# zx80_SD_12_smd_build006_7_STM32.net
KiCad netlist of a schematic drawn in EAGLE
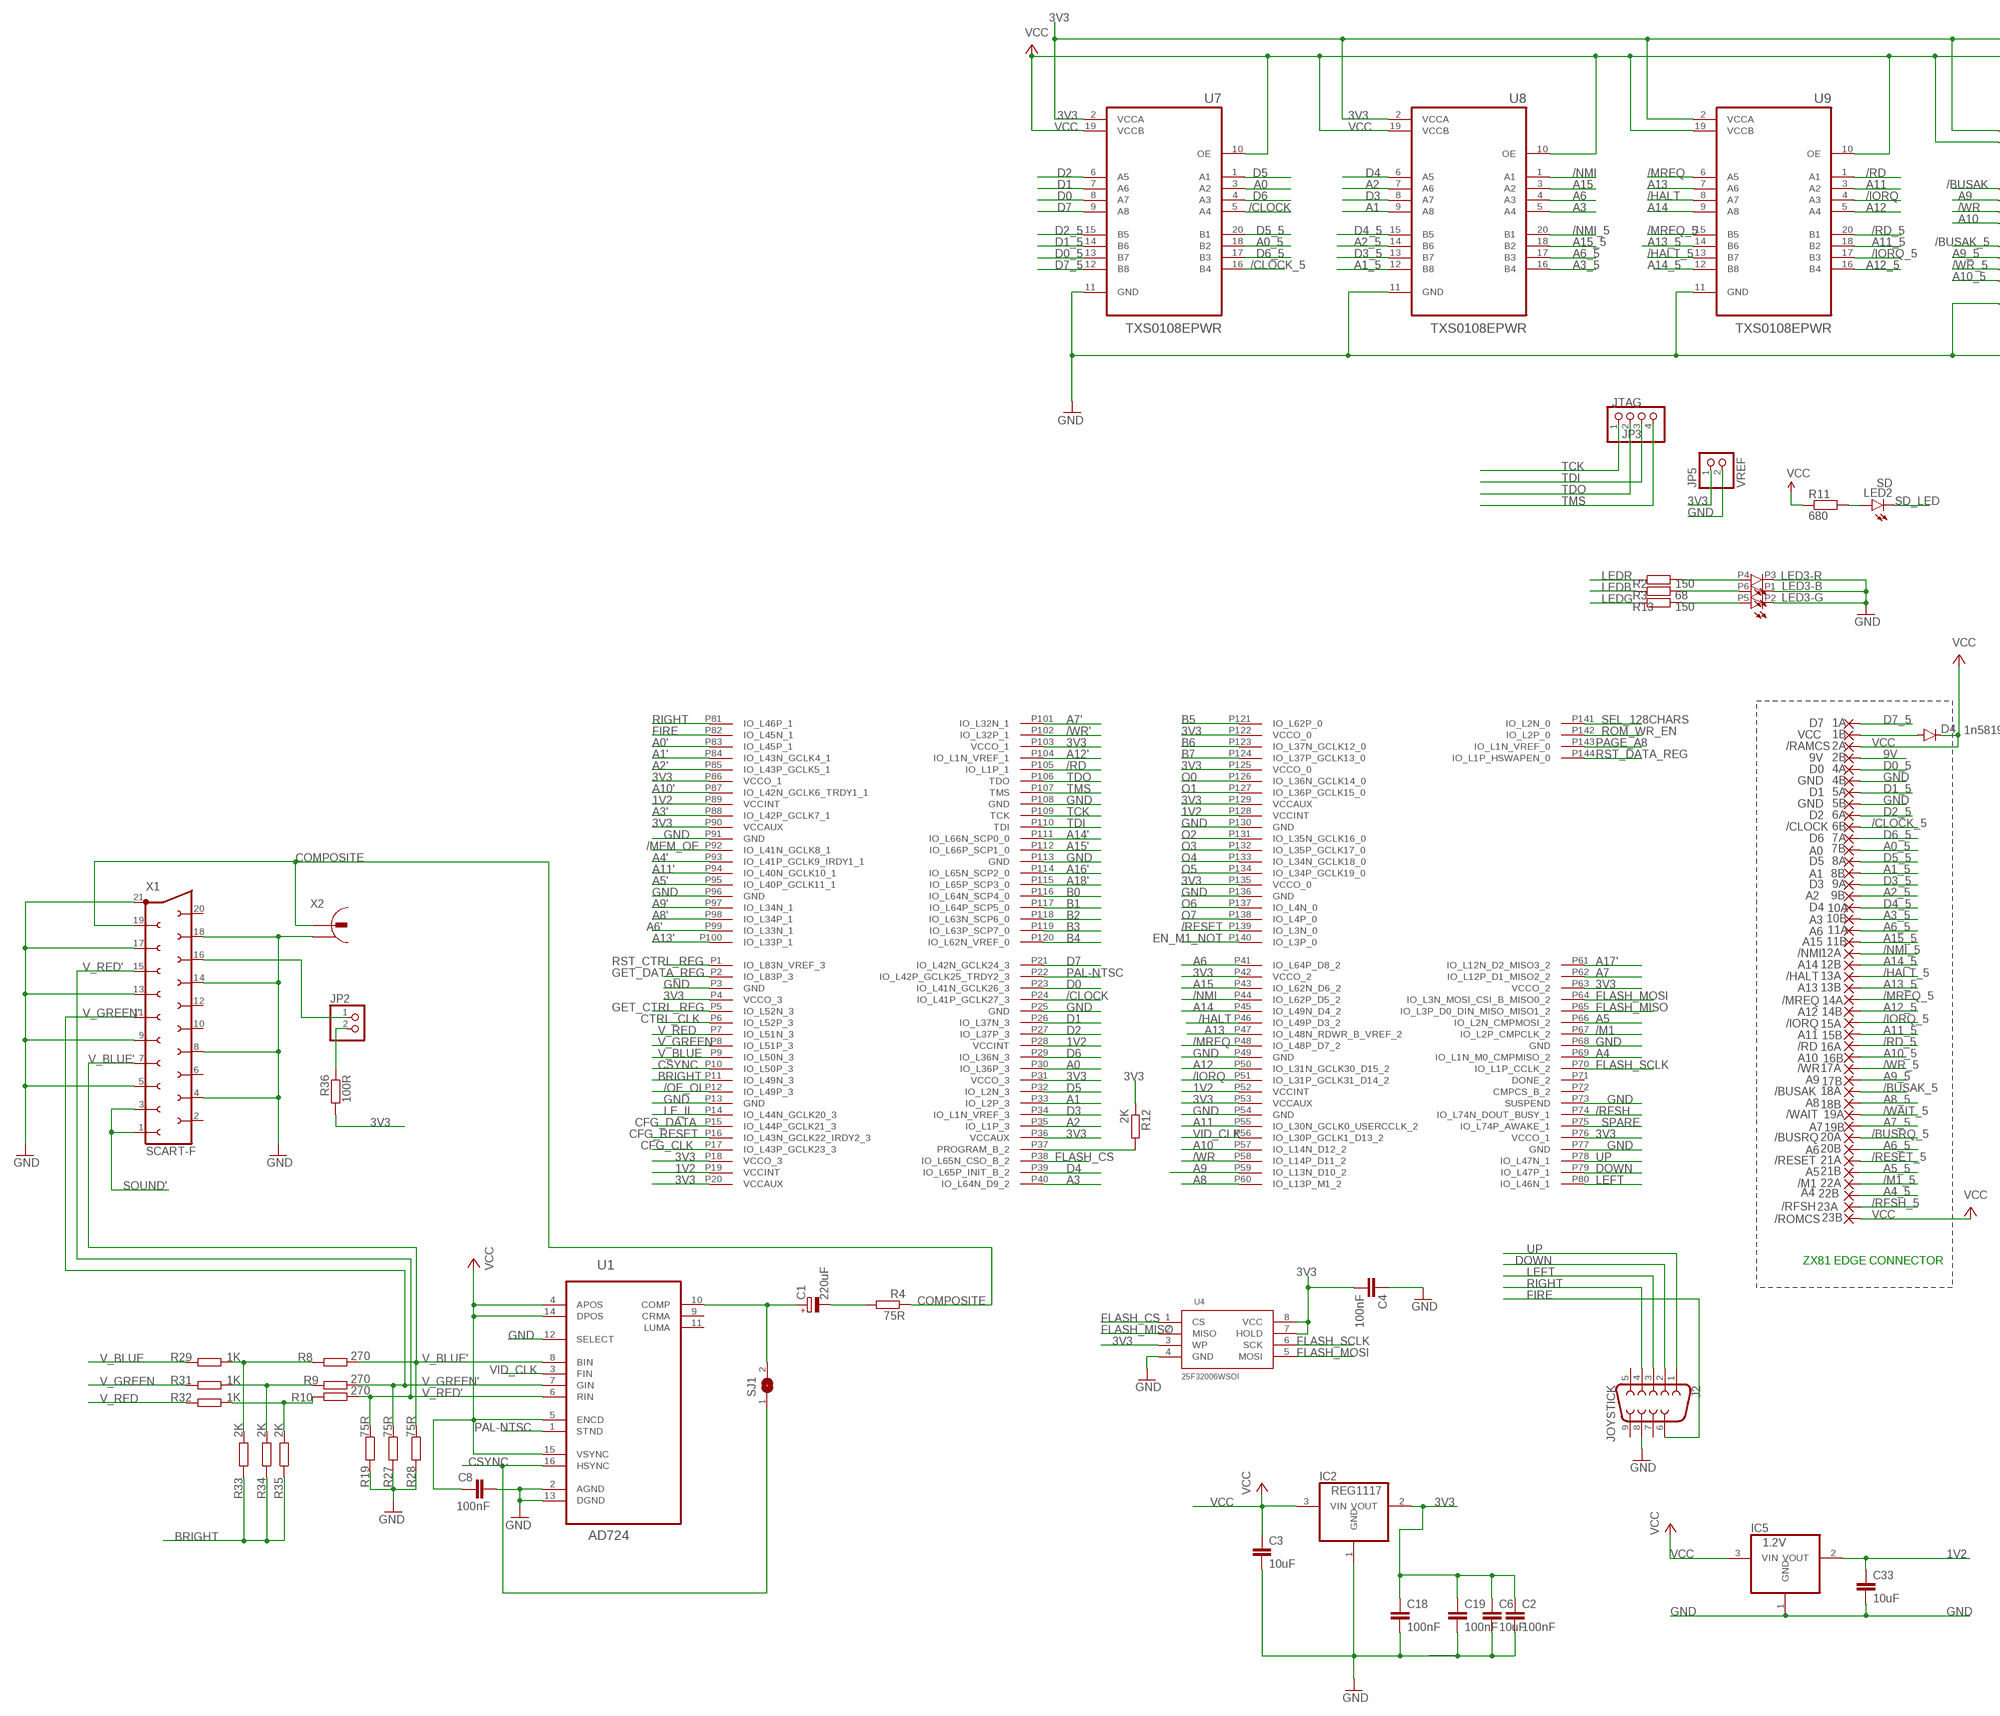
[diagram p0: schematic, sheet 1, part 1 of 2]
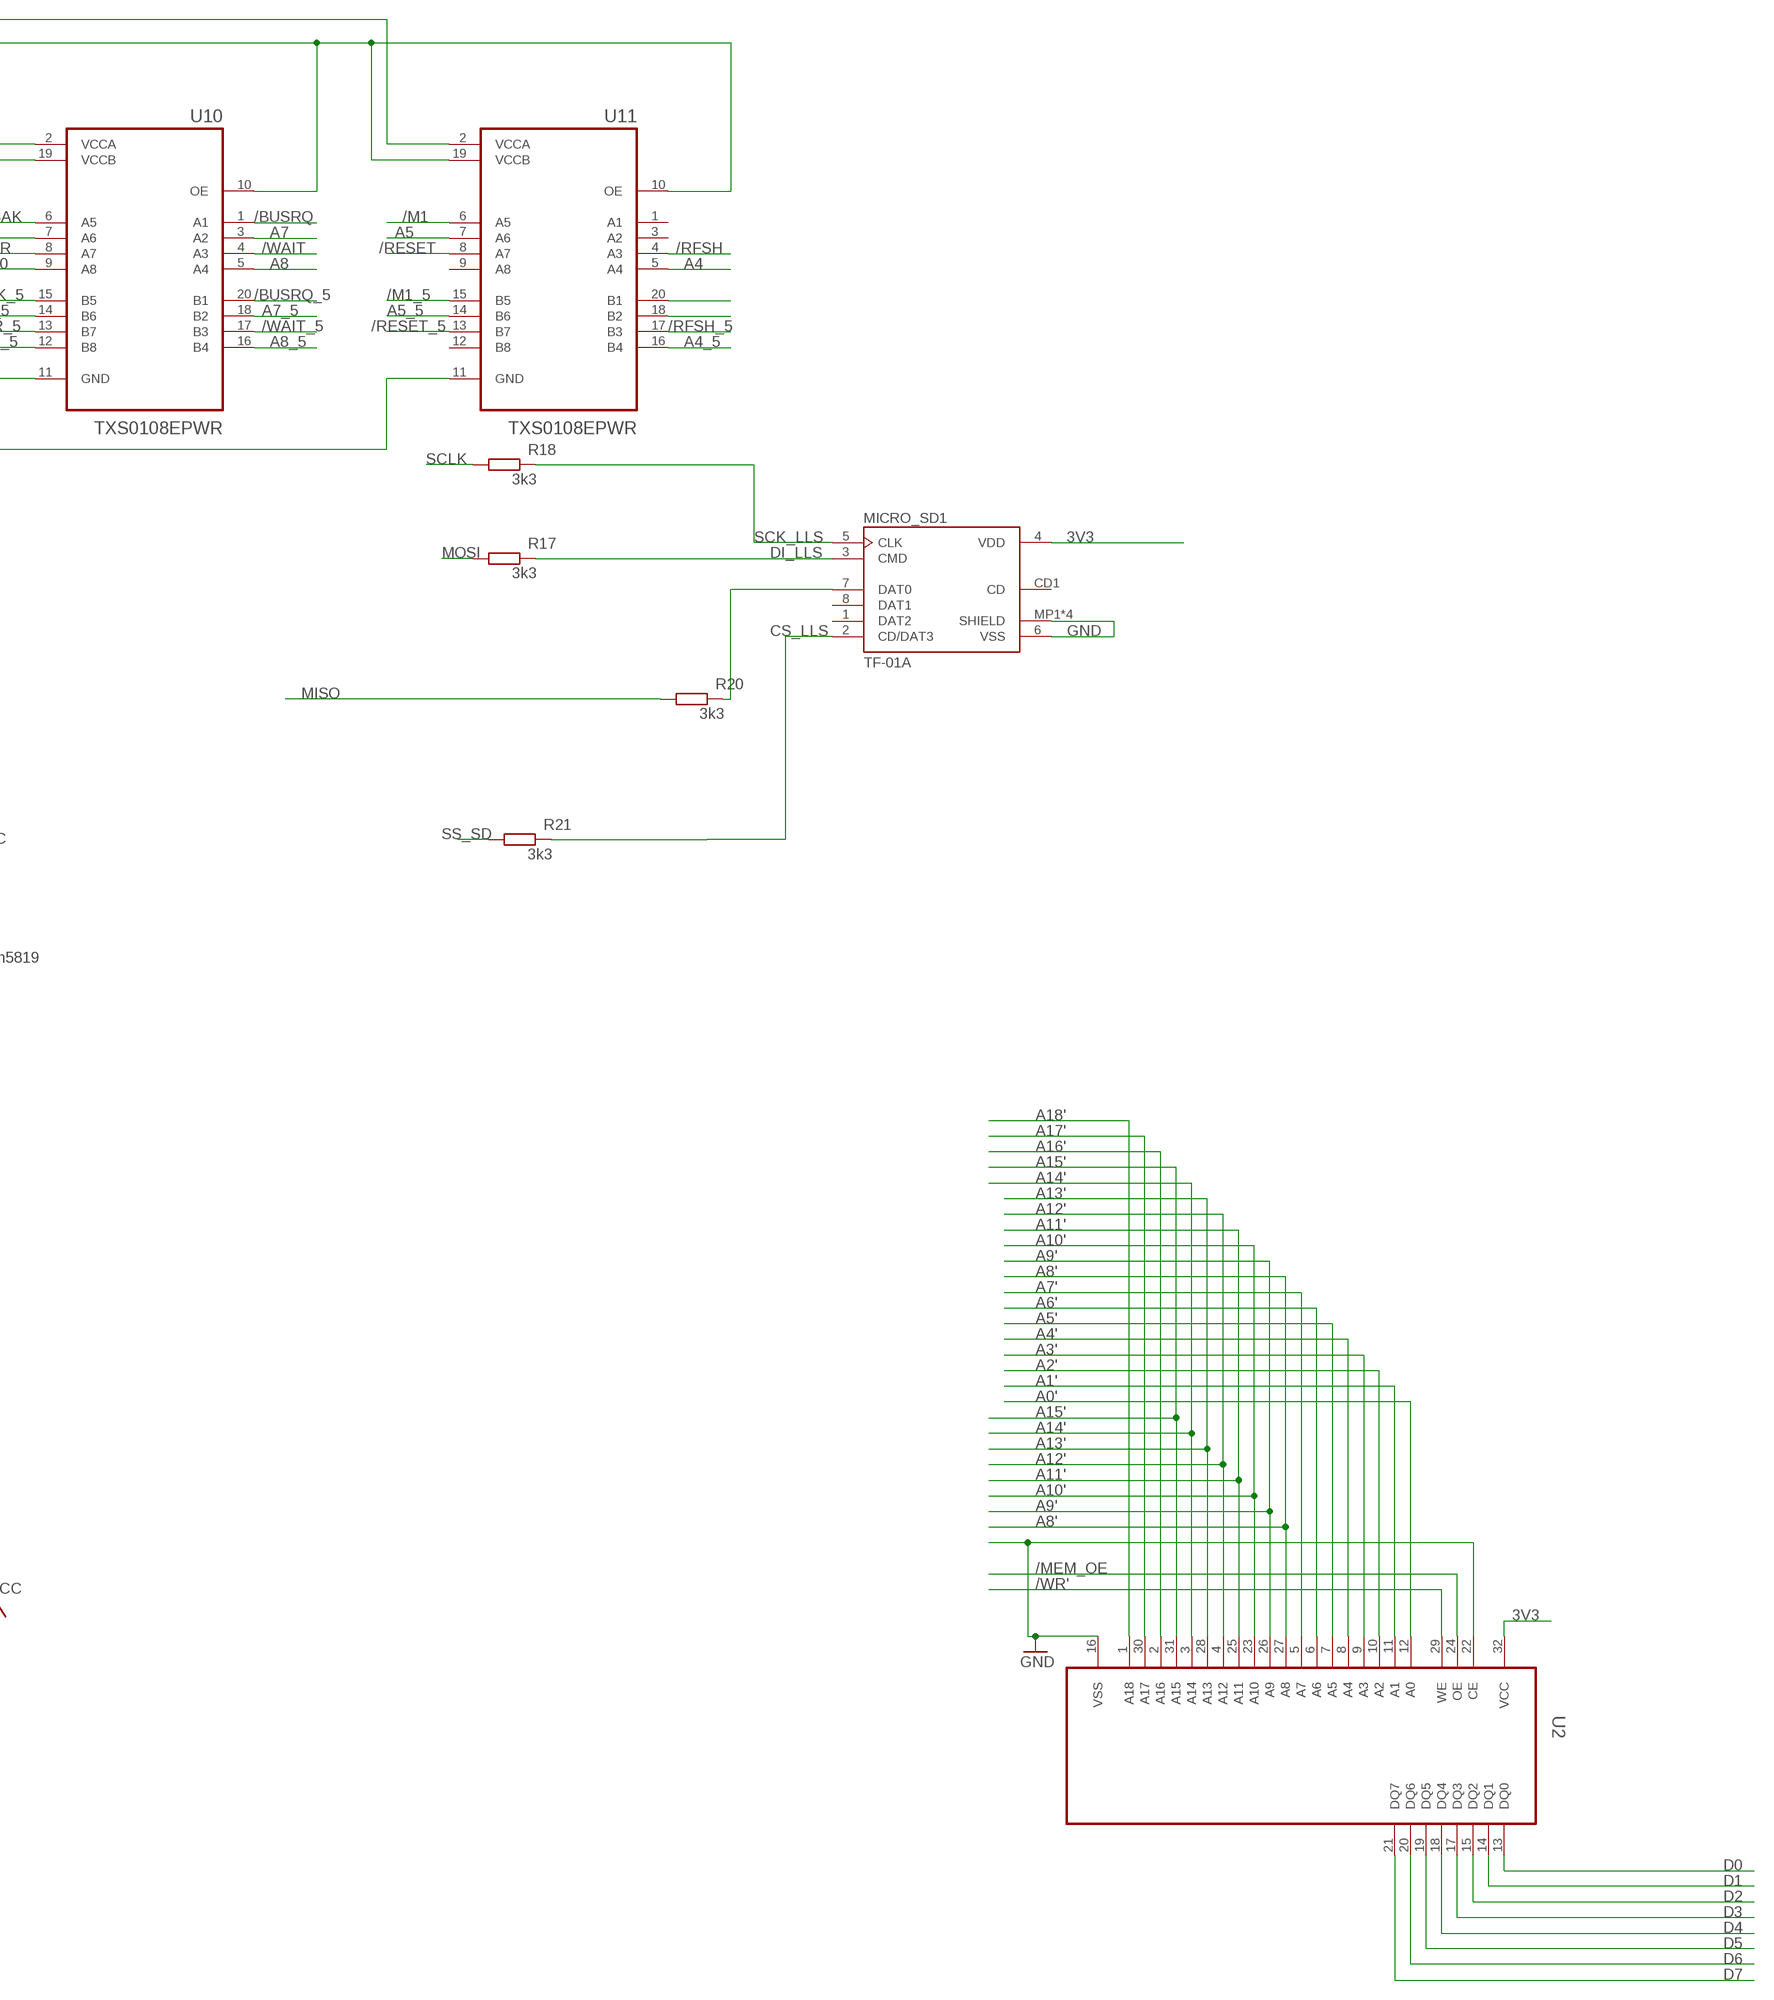
[diagram p1: schematic, sheet 1, part 2 of 2]
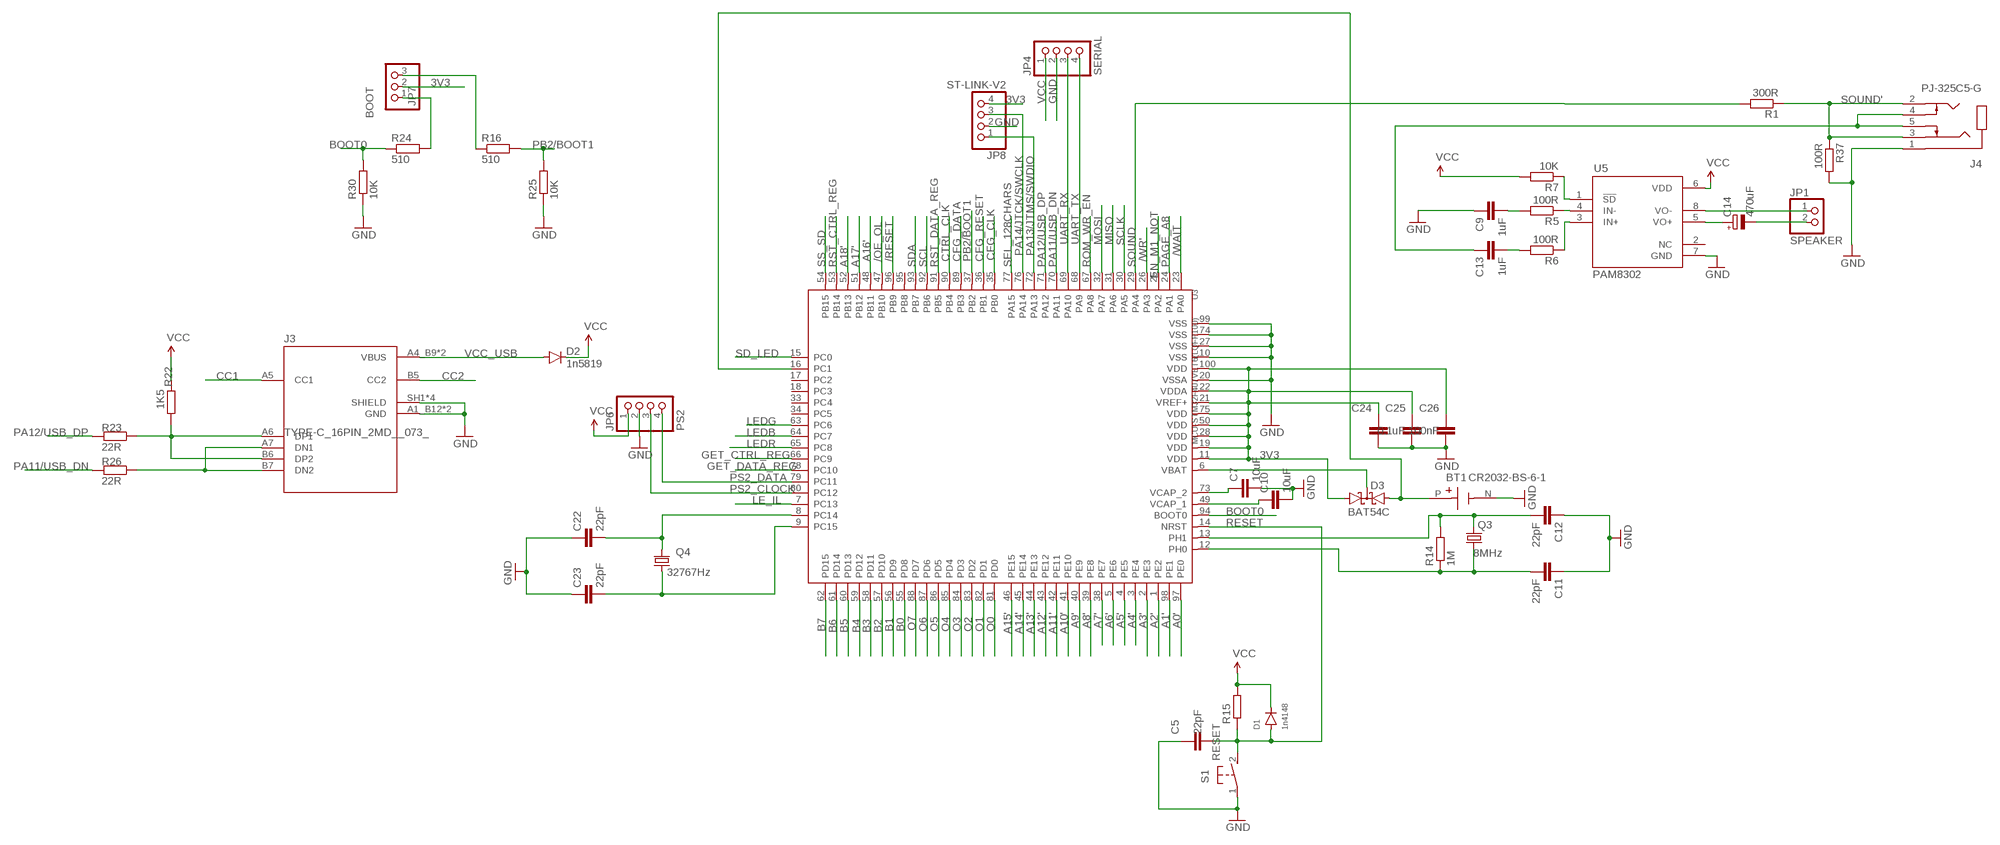
[diagram p2: schematic, sheet 2]

(export (version "E")
  (design (tool "Eeschema 10.0.6"))
  (components
    (comp (ref "BT1")
      (value "CR2032-BS-6-1")
      (footprint "eagle-import:BAT_CR2032-BS-6-1")
      (fields (field (name "MF") "Shenzhen Q&J Electronics Co. Ltd"))
      (libsource (lib "eagle-import") (part "CR2032-BS-6-1"))
    )
    (comp (ref "C5")
      (value "22pF")
      (footprint "eagle-import:C0603")
      (libsource (lib "eagle-import") (part "C-EUC0603"))
    )
    (comp (ref "C7")
      (value "10uF")
      (footprint "eagle-import:C0603")
      (libsource (lib "eagle-import") (part "C-EUC0603"))
    )
    (comp (ref "C9")
      (value "1uF")
      (footprint "eagle-import:C0603")
      (libsource (lib "eagle-import") (part "C-EUC0603"))
    )
    (comp (ref "C10")
      (value "10uF")
      (footprint "eagle-import:C0603")
      (libsource (lib "eagle-import") (part "C-EUC0603"))
    )
    (comp (ref "C11")
      (value "22pF")
      (footprint "eagle-import:C0603")
      (libsource (lib "eagle-import") (part "C-EUC0603"))
    )
    (comp (ref "C12")
      (value "22pF")
      (footprint "eagle-import:C0603")
      (libsource (lib "eagle-import") (part "C-EUC0603"))
    )
    (comp (ref "C13")
      (value "1uF")
      (footprint "eagle-import:C0603")
      (libsource (lib "eagle-import") (part "C-EUC0603"))
    )
    (comp (ref "C14")
      (value "470uF")
      (footprint "eagle-import:UD-6,3X7,7_NICHICON")
      (libsource (lib "eagle-import") (part "CPOL-EUUD-6,3X7,7"))
    )
    (comp (ref "C22")
      (value "22pF")
      (footprint "eagle-import:C0603")
      (libsource (lib "eagle-import") (part "C-EUC0603"))
    )
    (comp (ref "C23")
      (value "22pF")
      (footprint "eagle-import:C0603")
      (libsource (lib "eagle-import") (part "C-EUC0603"))
    )
    (comp (ref "C24")
      (value "0.1uF")
      (footprint "eagle-import:C0603")
      (libsource (lib "eagle-import") (part "C-EUC0603"))
    )
    (comp (ref "C25")
      (value "0.1uF")
      (footprint "eagle-import:C0603")
      (libsource (lib "eagle-import") (part "C-EUC0603"))
    )
    (comp (ref "C26")
      (value "100nF")
      (footprint "eagle-import:C0603")
      (libsource (lib "eagle-import") (part "C-EUC0603"))
    )
    (comp (ref "D1")
      (value "1n4148")
      (footprint "eagle-import:SOD123")
      (libsource (lib "eagle-import") (part "DIODE-SOD123"))
    )
    (comp (ref "D2")
      (value "1n5819")
      (footprint "eagle-import:SOD323-W")
      (libsource (lib "eagle-import") (part "DIODE-SOD323-W"))
    )
    (comp (ref "D3")
      (value "BAT54C")
      (footprint "eagle-import:SOT23")
      (libsource (lib "eagle-import") (part "BAT54C"))
    )
    (comp (ref "J3")
      (value "TYPE-C_16PIN_2MD__073_")
      (footprint "eagle-import:SHOUHAN_TYPE-C_16PIN_2MD__073_")
      (fields (field (name "MF") "Shouhan") (field (name "MP") "TYPE-C 16PIN 2MD (073)"))
      (libsource (lib "eagle-import") (part "TYPE-C_16PIN_2MD__073_"))
    )
    (comp (ref "J4")
      (value "PJ-325C5-G")
      (footprint "eagle-import:XKB_PJ-325C5-G")
      (fields (field (name "MF") "XKB Connection"))
      (libsource (lib "eagle-import") (part "PJ-325C5-G"))
    )
    (comp (ref "JP1")
      (value "SPEAKER")
      (footprint "eagle-import:1X02")
      (libsource (lib "eagle-import") (part "PINHD-1X2"))
    )
    (comp (ref "JP4")
      (value "SERIAL")
      (footprint "eagle-import:1X04")
      (libsource (lib "eagle-import") (part "PINHD-1X4"))
    )
    (comp (ref "JP6")
      (value "PS2")
      (footprint "eagle-import:1X04")
      (libsource (lib "eagle-import") (part "PINHD-1X4"))
    )
    (comp (ref "JP7")
      (value "BOOT")
      (footprint "eagle-import:1X03")
      (libsource (lib "eagle-import") (part "PINHD-1X3"))
    )
    (comp (ref "JP8")
      (value "ST-LINK-V2")
      (footprint "eagle-import:1X04")
      (libsource (lib "eagle-import") (part "PINHD-1X4"))
    )
    (comp (ref "Q3")
      (value "8MHz")
      (footprint "eagle-import:3.2X2.5_KX-7")
      (libsource (lib "eagle-import") (part "KX-7"))
    )
    (comp (ref "Q4")
      (value "32767Hz")
      (footprint "eagle-import:3.2X1.5")
      (libsource (lib "eagle-import") (part "KX-327-NHT"))
    )
    (comp (ref "R1")
      (value "300R")
      (footprint "eagle-import:R0603")
      (libsource (lib "eagle-import") (part "R-EU_R0603"))
    )
    (comp (ref "R5")
      (value "100R")
      (footprint "eagle-import:R0603")
      (libsource (lib "eagle-import") (part "R-EU_R0603"))
    )
    (comp (ref "R6")
      (value "100R")
      (footprint "eagle-import:R0603")
      (libsource (lib "eagle-import") (part "R-EU_R0603"))
    )
    (comp (ref "R7")
      (value "10K")
      (footprint "eagle-import:R0603")
      (libsource (lib "eagle-import") (part "R-EU_R0603"))
    )
    (comp (ref "R14")
      (value "1M")
      (footprint "eagle-import:R0402")
      (libsource (lib "eagle-import") (part "R-EU_R0402"))
    )
    (comp (ref "R15")
      (value "3k3")
      (footprint "eagle-import:R0603")
      (libsource (lib "eagle-import") (part "R-EU_R0603"))
    )
    (comp (ref "R16")
      (value "510")
      (footprint "eagle-import:R0603")
      (libsource (lib "eagle-import") (part "R-EU_R0603"))
    )
    (comp (ref "R22")
      (value "1K5")
      (footprint "eagle-import:R0603")
      (libsource (lib "eagle-import") (part "R-EU_R0603"))
    )
    (comp (ref "R23")
      (value "22R")
      (footprint "eagle-import:R0603")
      (libsource (lib "eagle-import") (part "R-EU_R0603"))
    )
    (comp (ref "R24")
      (value "510")
      (footprint "eagle-import:R0603")
      (libsource (lib "eagle-import") (part "R-EU_R0603"))
    )
    (comp (ref "R25")
      (value "10K")
      (footprint "eagle-import:R0603")
      (libsource (lib "eagle-import") (part "R-EU_R0603"))
    )
    (comp (ref "R26")
      (value "22R")
      (footprint "eagle-import:R0603")
      (libsource (lib "eagle-import") (part "R-EU_R0603"))
    )
    (comp (ref "R30")
      (value "10K")
      (footprint "eagle-import:R0603")
      (libsource (lib "eagle-import") (part "R-EU_R0603"))
    )
    (comp (ref "R37")
      (value "100R")
      (footprint "eagle-import:R0603")
      (libsource (lib "eagle-import") (part "R-EU_R0603"))
    )
    (comp (ref "S1")
      (value "RESET")
      (footprint "eagle-import:B3F-31XX")
      (fields (field (name "MPN") "B3F-3100"))
      (libsource (lib "eagle-import") (part "31-XX"))
    )
    (comp (ref "U3")
      (value "MCU-STM32F407VET6(LQFP100)")
      (footprint "eagle-import:LQFP100-0.5-13.8X13.8MM")
      (fields (field (name "MF") "STMicroelectronics") (field (name "MP") "STM32F407VET6"))
      (libsource (lib "eagle-import") (part "MCU-STM32F407VET6(LQFP100)"))
    )
    (comp (ref "U5")
      (value "PAM8302")
      (footprint "eagle-import:SOIC127P600X170-8N")
      (fields (field (name "MF") "Diodes Inc.") (field (name "MP") "PAM8302AADCR"))
      (libsource (lib "eagle-import") (part "PAM8302AADCR"))
    )
    (comp (ref "1A")
      (value "D7")
      (footprint "eagle-import:EDGEPIN")
      (libsource (lib "eagle-import") (part "SMD2EDGEPIN"))
    )
    (comp (ref "1B")
      (value "VCC")
      (footprint "eagle-import:EDGEPIN")
      (libsource (lib "eagle-import") (part "SMD2EDGEPIN"))
    )
    (comp (ref "2A")
      (value "/RAMCS")
      (footprint "eagle-import:EDGEPIN")
      (libsource (lib "eagle-import") (part "SMD2EDGEPIN"))
    )
    (comp (ref "2B")
      (value "9V")
      (footprint "eagle-import:EDGEPIN")
      (libsource (lib "eagle-import") (part "SMD2EDGEPIN"))
    )
    (comp (ref "4A")
      (value "D0")
      (footprint "eagle-import:EDGEPIN")
      (libsource (lib "eagle-import") (part "SMD2EDGEPIN"))
    )
    (comp (ref "4B")
      (value "GND")
      (footprint "eagle-import:EDGEPIN")
      (libsource (lib "eagle-import") (part "SMD2EDGEPIN"))
    )
    (comp (ref "5A")
      (value "D1")
      (footprint "eagle-import:EDGEPIN")
      (libsource (lib "eagle-import") (part "SMD2EDGEPIN"))
    )
    (comp (ref "5B")
      (value "GND")
      (footprint "eagle-import:EDGEPIN")
      (libsource (lib "eagle-import") (part "SMD2EDGEPIN"))
    )
    (comp (ref "6A")
      (value "D2")
      (footprint "eagle-import:EDGEPIN")
      (libsource (lib "eagle-import") (part "SMD2EDGEPIN"))
    )
    (comp (ref "6B")
      (value "/CLOCK")
      (footprint "eagle-import:EDGEPIN")
      (libsource (lib "eagle-import") (part "SMD2EDGEPIN"))
    )
    (comp (ref "7A")
      (value "D6")
      (footprint "eagle-import:EDGEPIN")
      (libsource (lib "eagle-import") (part "SMD2EDGEPIN"))
    )
    (comp (ref "7B")
      (value "A0")
      (footprint "eagle-import:EDGEPIN")
      (libsource (lib "eagle-import") (part "SMD2EDGEPIN"))
    )
    (comp (ref "8A")
      (value "D5")
      (footprint "eagle-import:EDGEPIN")
      (libsource (lib "eagle-import") (part "SMD2EDGEPIN"))
    )
    (comp (ref "8B")
      (value "A1")
      (footprint "eagle-import:EDGEPIN")
      (libsource (lib "eagle-import") (part "SMD2EDGEPIN"))
    )
    (comp (ref "9A")
      (value "D3")
      (footprint "eagle-import:EDGEPIN")
      (libsource (lib "eagle-import") (part "SMD2EDGEPIN"))
    )
    (comp (ref "9B")
      (value "A2")
      (footprint "eagle-import:EDGEPIN")
      (libsource (lib "eagle-import") (part "SMD2EDGEPIN"))
    )
    (comp (ref "10A")
      (value "D4")
      (footprint "eagle-import:EDGEPIN")
      (libsource (lib "eagle-import") (part "SMD2EDGEPIN"))
    )
    (comp (ref "10B")
      (value "A3")
      (footprint "eagle-import:EDGEPIN")
      (libsource (lib "eagle-import") (part "SMD2EDGEPIN"))
    )
    (comp (ref "11A")
      (value "A6")
      (footprint "eagle-import:EDGEPIN")
      (libsource (lib "eagle-import") (part "SMD2EDGEPIN"))
    )
    (comp (ref "11B")
      (value "A15")
      (footprint "eagle-import:EDGEPIN")
      (libsource (lib "eagle-import") (part "SMD2EDGEPIN"))
    )
    (comp (ref "12A")
      (value "/NMI")
      (footprint "eagle-import:EDGEPIN")
      (libsource (lib "eagle-import") (part "SMD2EDGEPIN"))
    )
    (comp (ref "12B")
      (value "A14")
      (footprint "eagle-import:EDGEPIN")
      (libsource (lib "eagle-import") (part "SMD2EDGEPIN"))
    )
    (comp (ref "13A")
      (value "/HALT")
      (footprint "eagle-import:EDGEPIN")
      (libsource (lib "eagle-import") (part "SMD2EDGEPIN"))
    )
    (comp (ref "13B")
      (value "A13")
      (footprint "eagle-import:EDGEPIN")
      (libsource (lib "eagle-import") (part "SMD2EDGEPIN"))
    )
    (comp (ref "14A")
      (value "/MREQ")
      (footprint "eagle-import:EDGEPIN")
      (libsource (lib "eagle-import") (part "SMD2EDGEPIN"))
    )
    (comp (ref "14B")
      (value "A12")
      (footprint "eagle-import:EDGEPIN")
      (libsource (lib "eagle-import") (part "SMD2EDGEPIN"))
    )
    (comp (ref "15A")
      (value "/IORQ")
      (footprint "eagle-import:EDGEPIN")
      (libsource (lib "eagle-import") (part "SMD2EDGEPIN"))
    )
    (comp (ref "15B")
      (value "A11")
      (footprint "eagle-import:EDGEPIN")
      (libsource (lib "eagle-import") (part "SMD2EDGEPIN"))
    )
    (comp (ref "16A")
      (value "/RD")
      (footprint "eagle-import:EDGEPIN")
      (libsource (lib "eagle-import") (part "SMD2EDGEPIN"))
    )
    (comp (ref "16B")
      (value "A10")
      (footprint "eagle-import:EDGEPIN")
      (libsource (lib "eagle-import") (part "SMD2EDGEPIN"))
    )
    (comp (ref "17A")
      (value "/WR")
      (footprint "eagle-import:EDGEPIN")
      (libsource (lib "eagle-import") (part "SMD2EDGEPIN"))
    )
    (comp (ref "17B")
      (value "A9")
      (footprint "eagle-import:EDGEPIN")
      (libsource (lib "eagle-import") (part "SMD2EDGEPIN"))
    )
    (comp (ref "18A")
      (value "/BUSAK")
      (footprint "eagle-import:EDGEPIN")
      (libsource (lib "eagle-import") (part "SMD2EDGEPIN"))
    )
    (comp (ref "18B")
      (value "A8")
      (footprint "eagle-import:EDGEPIN")
      (libsource (lib "eagle-import") (part "SMD2EDGEPIN"))
    )
    (comp (ref "19A")
      (value "/WAIT")
      (footprint "eagle-import:EDGEPIN")
      (libsource (lib "eagle-import") (part "SMD2EDGEPIN"))
    )
    (comp (ref "19B")
      (value "A7")
      (footprint "eagle-import:EDGEPIN")
      (libsource (lib "eagle-import") (part "SMD2EDGEPIN"))
    )
    (comp (ref "20A")
      (value "/BUSRQ")
      (footprint "eagle-import:EDGEPIN")
      (libsource (lib "eagle-import") (part "SMD2EDGEPIN"))
    )
    (comp (ref "20B")
      (value "A6")
      (footprint "eagle-import:EDGEPIN")
      (libsource (lib "eagle-import") (part "SMD2EDGEPIN"))
    )
    (comp (ref "21A")
      (value "/RESET")
      (footprint "eagle-import:EDGEPIN")
      (libsource (lib "eagle-import") (part "SMD2EDGEPIN"))
    )
    (comp (ref "21B")
      (value "A5")
      (footprint "eagle-import:EDGEPIN")
      (libsource (lib "eagle-import") (part "SMD2EDGEPIN"))
    )
    (comp (ref "22A")
      (value "/M1")
      (footprint "eagle-import:EDGEPIN")
      (libsource (lib "eagle-import") (part "SMD2EDGEPIN"))
    )
    (comp (ref "22B")
      (value "A4")
      (footprint "eagle-import:EDGEPIN")
      (libsource (lib "eagle-import") (part "SMD2EDGEPIN"))
    )
    (comp (ref "23A")
      (value "/RFSH")
      (footprint "eagle-import:EDGEPIN")
      (libsource (lib "eagle-import") (part "SMD2EDGEPIN"))
    )
    (comp (ref "23B")
      (value "/ROMCS")
      (footprint "eagle-import:EDGEPIN")
      (libsource (lib "eagle-import") (part "SMD2EDGEPIN"))
    )
    (comp (ref "C1")
      (value "220uF")
      (footprint "eagle-import:UD-6,3X7,7_NICHICON")
      (libsource (lib "eagle-import") (part "CPOL-EUUD-6,3X7,7"))
    )
    (comp (ref "C2")
      (value "100nF")
      (footprint "eagle-import:C0603")
      (libsource (lib "eagle-import") (part "C-EUC0603"))
    )
    (comp (ref "C3")
      (value "10uF")
      (footprint "eagle-import:C0603")
      (libsource (lib "eagle-import") (part "C-EUC0603"))
    )
    (comp (ref "C4")
      (value "100nF")
      (footprint "eagle-import:C0603")
      (libsource (lib "eagle-import") (part "C-EUC0603"))
    )
    (comp (ref "C6")
      (value "10uF")
      (footprint "eagle-import:C0603")
      (libsource (lib "eagle-import") (part "C-EUC0603"))
    )
    (comp (ref "C8")
      (value "100nF")
      (footprint "eagle-import:C0603K")
      (libsource (lib "eagle-import") (part "C-EUC0603K"))
    )
    (comp (ref "C18")
      (value "100nF")
      (footprint "eagle-import:C0603")
      (libsource (lib "eagle-import") (part "C-EUC0603"))
    )
    (comp (ref "C19")
      (value "100nF")
      (footprint "eagle-import:C0603")
      (libsource (lib "eagle-import") (part "C-EUC0603"))
    )
    (comp (ref "C33")
      (value "10uF")
      (footprint "eagle-import:C0603")
      (libsource (lib "eagle-import") (part "C-EUC0603"))
    )
    (comp (ref "D4")
      (value "1n5819")
      (footprint "eagle-import:SOD323-W")
      (libsource (lib "eagle-import") (part "DIODE-SOD323-W"))
    )
    (comp (ref "IC2")
      (value "REG1117")
      (footprint "eagle-import:SOT223")
      (libsource (lib "eagle-import") (part "REG1117"))
    )
    (comp (ref "IC5")
      (value "1.2V")
      (footprint "eagle-import:SOT223")
      (fields (field (name "MPN") "REG1117"))
      (libsource (lib "eagle-import") (part "REG1117"))
    )
    (comp (ref "J2")
      (value "JOYSTICK")
      (footprint "eagle-import:DB9_MALE")
      (libsource (lib "eagle-import") (part "DB9MALE"))
    )
    (comp (ref "JP2")
      (value "PINHD-1X2")
      (footprint "eagle-import:1X02")
      (libsource (lib "eagle-import") (part "PINHD-1X2"))
    )
    (comp (ref "JP3")
      (value "JTAG")
      (footprint "eagle-import:1X04")
      (libsource (lib "eagle-import") (part "PINHD-1X4"))
    )
    (comp (ref "JP5")
      (value "VREF")
      (footprint "eagle-import:1X02")
      (libsource (lib "eagle-import") (part "PINHD-1X2"))
    )
    (comp (ref "LED2")
      (value "SD")
      (footprint "eagle-import:CHIPLED_0805")
      (libsource (lib "eagle-import") (part "LEDCHIPLED_0805"))
    )
    (comp (ref "LED3")
      (value "STATUS")
      (footprint "eagle-import:3535-PLCC6")
      (libsource (lib "eagle-import") (part "3535RGB3535RGB"))
    )
    (comp (ref "MICRO_SD1")
      (value "TF-01A")
      (footprint "eagle-import:TF-01A")
      (fields (field (name "MF") "HRO Electronics Co., Ltd."))
      (libsource (lib "eagle-import") (part "TF-01A"))
    )
    (comp (ref "R2")
      (value "150")
      (footprint "eagle-import:R0603")
      (libsource (lib "eagle-import") (part "R-EU_R0603"))
    )
    (comp (ref "R3")
      (value "68")
      (footprint "eagle-import:R0603")
      (libsource (lib "eagle-import") (part "R-EU_R0603"))
    )
    (comp (ref "R4")
      (value "75R")
      (footprint "eagle-import:R0603")
      (libsource (lib "eagle-import") (part "R-EU_R0603"))
    )
    (comp (ref "R8")
      (value "270")
      (footprint "eagle-import:R0603")
      (libsource (lib "eagle-import") (part "R-EU_R0603"))
    )
    (comp (ref "R9")
      (value "270")
      (footprint "eagle-import:R0603")
      (libsource (lib "eagle-import") (part "R-EU_R0603"))
    )
    (comp (ref "R10")
      (value "270")
      (footprint "eagle-import:R0603")
      (libsource (lib "eagle-import") (part "R-EU_R0603"))
    )
    (comp (ref "R11")
      (value "680")
      (footprint "eagle-import:R0603")
      (libsource (lib "eagle-import") (part "R-EU_R0603"))
    )
    (comp (ref "R12")
      (value "2K")
      (footprint "eagle-import:R0402")
      (libsource (lib "eagle-import") (part "R-EU_R0402"))
    )
    (comp (ref "R13")
      (value "150")
      (footprint "eagle-import:R0603")
      (libsource (lib "eagle-import") (part "R-EU_R0603"))
    )
    (comp (ref "R17")
      (value "3k3")
      (footprint "eagle-import:R0603")
      (libsource (lib "eagle-import") (part "R-EU_R0603"))
    )
    (comp (ref "R18")
      (value "3k3")
      (footprint "eagle-import:R0603")
      (libsource (lib "eagle-import") (part "R-EU_R0603"))
    )
    (comp (ref "R19")
      (value "75R")
      (footprint "eagle-import:R0603")
      (libsource (lib "eagle-import") (part "R-EU_R0603"))
    )
    (comp (ref "R20")
      (value "3k3")
      (footprint "eagle-import:R0603")
      (libsource (lib "eagle-import") (part "R-EU_R0603"))
    )
    (comp (ref "R21")
      (value "3k3")
      (footprint "eagle-import:R0603")
      (libsource (lib "eagle-import") (part "R-EU_R0603"))
    )
    (comp (ref "R27")
      (value "75R")
      (footprint "eagle-import:R0603")
      (libsource (lib "eagle-import") (part "R-EU_R0603"))
    )
    (comp (ref "R28")
      (value "75R")
      (footprint "eagle-import:R0603")
      (libsource (lib "eagle-import") (part "R-EU_R0603"))
    )
    (comp (ref "R29")
      (value "1K")
      (footprint "eagle-import:R0402")
      (libsource (lib "eagle-import") (part "R-EU_R0402"))
    )
    (comp (ref "R31")
      (value "1K")
      (footprint "eagle-import:R0402")
      (libsource (lib "eagle-import") (part "R-EU_R0402"))
    )
    (comp (ref "R32")
      (value "1K")
      (footprint "eagle-import:R0402")
      (libsource (lib "eagle-import") (part "R-EU_R0402"))
    )
    (comp (ref "R33")
      (value "2K")
      (footprint "eagle-import:R0402")
      (libsource (lib "eagle-import") (part "R-EU_R0402"))
    )
    (comp (ref "R34")
      (value "2K")
      (footprint "eagle-import:R0402")
      (libsource (lib "eagle-import") (part "R-EU_R0402"))
    )
    (comp (ref "R35")
      (value "2K")
      (footprint "eagle-import:R0402")
      (libsource (lib "eagle-import") (part "R-EU_R0402"))
    )
    (comp (ref "R36")
      (value "100R")
      (footprint "eagle-import:R0603")
      (libsource (lib "eagle-import") (part "R-EU_R0603"))
    )
    (comp (ref "SJ1") (value "SJ") (footprint "eagle-import:SJ") (libsource (lib "eagle-import") (part "SJ")))
    (comp (ref "U1")
      (value "AD724")
      (footprint "eagle-import:SOIC127P1032X265-16N")
      (fields (field (name "MF") "Analog Devices") (field (name "MP") "AD724JR"))
      (libsource (lib "eagle-import") (part "AD724JRZ"))
    )
    (comp (ref "U2")
      (value "AS6C4008")
      (footprint "eagle-import:SOP32-5")
      (libsource (lib "eagle-import") (part "AS6C4008-55SINSOP5"))
    )
    (comp (ref "U4")
      (value "25F32006WSOI")
      (footprint "eagle-import:SO08-EIAJ")
      (libsource (lib "eagle-import") (part "SPI_FLASH-X25XXSMD1"))
    )
    (comp (ref "U6")
      (value "XC6SLX9-2TQG144C")
      (footprint "eagle-import:TQ144")
      (fields (field (name "MF") "Xilinx Inc."))
      (libsource (lib "eagle-import") (part "XC6SLX9-2TQG144C"))
    )
    (comp (ref "U7")
      (value "TXS0108EPWR")
      (footprint "eagle-import:SOP65P640X120-20N")
      (fields (field (name "MF") "Texas Instruments"))
      (libsource (lib "eagle-import") (part "TXS0108EPWR"))
    )
    (comp (ref "U8")
      (value "TXS0108EPWR")
      (footprint "eagle-import:SOP65P640X120-20N")
      (fields (field (name "MF") "Texas Instruments"))
      (libsource (lib "eagle-import") (part "TXS0108EPWR"))
    )
    (comp (ref "U9")
      (value "TXS0108EPWR")
      (footprint "eagle-import:SOP65P640X120-20N")
      (fields (field (name "MF") "Texas Instruments"))
      (libsource (lib "eagle-import") (part "TXS0108EPWR"))
    )
    (comp (ref "U10")
      (value "TXS0108EPWR")
      (footprint "eagle-import:SOP65P640X120-20N")
      (fields (field (name "MF") "Texas Instruments"))
      (libsource (lib "eagle-import") (part "TXS0108EPWR"))
    )
    (comp (ref "U11")
      (value "TXS0108EPWR")
      (footprint "eagle-import:SOP65P640X120-20N")
      (fields (field (name "MF") "Texas Instruments"))
      (libsource (lib "eagle-import") (part "TXS0108EPWR"))
    )
    (comp (ref "X1")
      (value "SCART-F")
      (footprint "eagle-import:SCART-F")
      (libsource (lib "eagle-import") (part "SCART-F"))
    )
    (comp (ref "X2")
      (value "CON-CONRAD_736880-2P")
      (footprint "eagle-import:3P")
      (libsource (lib "eagle-import") (part "CON-CONRAD_736880-2P"))
    )
  )
  (nets
    (net (code "1") (name "1V2") (class "Default")
      (node (ref "C33") (pin "1") (pinfunction "1_1") (pintype "passive"))
      (node (ref "IC5") (pin "2") (pinfunction "VOUT_2") (pintype "output"))
      (node (ref "U6") (pin "P128") (pinfunction "VCCINT_P128") (pintype "bidirectional"))
      (node (ref "U6") (pin "P19") (pinfunction "VCCINT_P19") (pintype "bidirectional"))
      (node (ref "U6") (pin "P28") (pinfunction "VCCINT_P28") (pintype "bidirectional"))
      (node (ref "U6") (pin "P52") (pinfunction "VCCINT_P52") (pintype "bidirectional"))
      (node (ref "U6") (pin "P89") (pinfunction "VCCINT_P89") (pintype "bidirectional"))
    )
    (net (code "2") (name "3V3") (class "Default")
      (node (ref "C18") (pin "1") (pinfunction "1_1") (pintype "passive"))
      (node (ref "C19") (pin "1") (pinfunction "1_1") (pintype "passive"))
      (node (ref "C2") (pin "1") (pinfunction "1_1") (pintype "passive"))
      (node (ref "C24") (pin "1") (pinfunction "1_1") (pintype "passive"))
      (node (ref "C25") (pin "1") (pinfunction "1_1") (pintype "passive"))
      (node (ref "C26") (pin "1") (pinfunction "1_1") (pintype "passive"))
      (node (ref "C4") (pin "2") (pinfunction "2_2") (pintype "passive"))
      (node (ref "C6") (pin "1") (pinfunction "1_1") (pintype "passive"))
      (node (ref "D3") (pin "1") (pinfunction "A1_1") (pintype "passive"))
      (node (ref "IC2") (pin "2") (pinfunction "VOUT_2") (pintype "output"))
      (node (ref "JP5") (pin "1") (pinfunction "1_1") (pintype "passive"))
      (node (ref "JP7") (pin "2") (pinfunction "2_2") (pintype "passive"))
      (node (ref "JP8") (pin "4") (pinfunction "4_4") (pintype "passive"))
      (node (ref "MICRO_SD1") (pin "4") (pinfunction "VDD_4") (pintype "power_in"))
      (node (ref "R12") (pin "1") (pinfunction "1_1") (pintype "passive"))
      (node (ref "R36") (pin "2") (pinfunction "2_2") (pintype "passive"))
      (node (ref "U10") (pin "2") (pinfunction "VCCA_2") (pintype "power_in"))
      (node (ref "U11") (pin "2") (pinfunction "VCCA_2") (pintype "power_in"))
      (node (ref "U2") (pin "32") (pinfunction "VCC_32") (pintype "power_in"))
      (node (ref "U3") (pin "100") (pinfunction "VDD_100") (pintype "bidirectional"))
      (node (ref "U3") (pin "11") (pinfunction "VDD_11") (pintype "bidirectional"))
      (node (ref "U3") (pin "19") (pinfunction "VDD_19") (pintype "bidirectional"))
      (node (ref "U3") (pin "21") (pinfunction "VREF+_21") (pintype "bidirectional"))
      (node (ref "U3") (pin "22") (pinfunction "VDDA_22") (pintype "bidirectional"))
      (node (ref "U3") (pin "28") (pinfunction "VDD_28") (pintype "bidirectional"))
      (node (ref "U3") (pin "50") (pinfunction "VDD_50") (pintype "bidirectional"))
      (node (ref "U3") (pin "75") (pinfunction "VDD_75") (pintype "bidirectional"))
      (node (ref "U4") (pin "3") (pinfunction "WP_3") (pintype "bidirectional"))
      (node (ref "U4") (pin "7") (pinfunction "HOLD_7") (pintype "bidirectional"))
      (node (ref "U4") (pin "8") (pinfunction "VCC_8") (pintype "power_in"))
      (node (ref "U6") (pin "P103") (pinfunction "VCCO_1_P103") (pintype "bidirectional"))
      (node (ref "U6") (pin "P122") (pinfunction "VCCO_0_P122") (pintype "bidirectional"))
      (node (ref "U6") (pin "P125") (pinfunction "VCCO_0_P125") (pintype "bidirectional"))
      (node (ref "U6") (pin "P129") (pinfunction "VCCAUX_P129") (pintype "bidirectional"))
      (node (ref "U6") (pin "P135") (pinfunction "VCCO_0_P135") (pintype "bidirectional"))
      (node (ref "U6") (pin "P18") (pinfunction "VCCO_3_P18") (pintype "bidirectional"))
      (node (ref "U6") (pin "P20") (pinfunction "VCCAUX_P20") (pintype "bidirectional"))
      (node (ref "U6") (pin "P31") (pinfunction "VCCO_3_P31") (pintype "bidirectional"))
      (node (ref "U6") (pin "P36") (pinfunction "VCCAUX_P36") (pintype "bidirectional"))
      (node (ref "U6") (pin "P4") (pinfunction "VCCO_3_P4") (pintype "bidirectional"))
      (node (ref "U6") (pin "P42") (pinfunction "VCCO_2_P42") (pintype "bidirectional"))
      (node (ref "U6") (pin "P53") (pinfunction "VCCAUX_P53") (pintype "bidirectional"))
      (node (ref "U6") (pin "P63") (pinfunction "VCCO_2_P63") (pintype "bidirectional"))
      (node (ref "U6") (pin "P76") (pinfunction "VCCO_1_P76") (pintype "bidirectional"))
      (node (ref "U6") (pin "P86") (pinfunction "VCCO_1_P86") (pintype "bidirectional"))
      (node (ref "U6") (pin "P90") (pinfunction "VCCAUX_P90") (pintype "bidirectional"))
      (node (ref "U7") (pin "2") (pinfunction "VCCA_2") (pintype "power_in"))
      (node (ref "U8") (pin "2") (pinfunction "VCCA_2") (pintype "power_in"))
      (node (ref "U9") (pin "2") (pinfunction "VCCA_2") (pintype "power_in"))
    )
    (net (code "3") (name "9V") (class "Default")
      (node (ref "2B") (pin "1") (pinfunction "P_1") (pintype "passive"))
    )
    (net (code "4") (name "A0") (class "Default")
      (node (ref "U6") (pin "P30") (pinfunction "IO_L36P_3_P30") (pintype "bidirectional"))
      (node (ref "U7") (pin "3") (pinfunction "A2_3") (pintype "bidirectional"))
    )
    (net (code "5") (name "A0'") (class "Default")
      (node (ref "U2") (pin "12") (pinfunction "A0_12") (pintype "input"))
      (node (ref "U3") (pin "97") (pinfunction "PE0_97") (pintype "bidirectional"))
      (node (ref "U6") (pin "P83") (pinfunction "IO_L45P_1_P83") (pintype "bidirectional"))
    )
    (net (code "6") (name "A0_5") (class "Default")
      (node (ref "7B") (pin "1") (pinfunction "P_1") (pintype "passive"))
      (node (ref "U7") (pin "18") (pinfunction "B2_18") (pintype "bidirectional"))
    )
    (net (code "7") (name "A1") (class "Default")
      (node (ref "U6") (pin "P33") (pinfunction "IO_L2P_3_P33") (pintype "bidirectional"))
      (node (ref "U8") (pin "9") (pinfunction "A8_9") (pintype "bidirectional"))
    )
    (net (code "8") (name "A1'") (class "Default")
      (node (ref "U2") (pin "11") (pinfunction "A1_11") (pintype "input"))
      (node (ref "U3") (pin "98") (pinfunction "PE1_98") (pintype "bidirectional"))
      (node (ref "U6") (pin "P84") (pinfunction "IO_L43N_GCLK4_1_P84") (pintype "bidirectional"))
    )
    (net (code "9") (name "A1_5") (class "Default")
      (node (ref "8B") (pin "1") (pinfunction "P_1") (pintype "passive"))
      (node (ref "U8") (pin "12") (pinfunction "B8_12") (pintype "bidirectional"))
    )
    (net (code "10") (name "A2") (class "Default")
      (node (ref "U6") (pin "P35") (pinfunction "IO_L1P_3_P35") (pintype "bidirectional"))
      (node (ref "U8") (pin "7") (pinfunction "A6_7") (pintype "bidirectional"))
    )
    (net (code "11") (name "A2'") (class "Default")
      (node (ref "U2") (pin "10") (pinfunction "A2_10") (pintype "input"))
      (node (ref "U3") (pin "1") (pinfunction "PE2_1") (pintype "bidirectional"))
      (node (ref "U6") (pin "P85") (pinfunction "IO_L43P_GCLK5_1_P85") (pintype "bidirectional"))
    )
    (net (code "12") (name "A2_5") (class "Default")
      (node (ref "9B") (pin "1") (pinfunction "P_1") (pintype "passive"))
      (node (ref "U8") (pin "14") (pinfunction "B6_14") (pintype "bidirectional"))
    )
    (net (code "13") (name "A3") (class "Default")
      (node (ref "U6") (pin "P40") (pinfunction "IO_L64N_D9_2_P40") (pintype "bidirectional"))
      (node (ref "U8") (pin "5") (pinfunction "A4_5") (pintype "bidirectional"))
    )
    (net (code "14") (name "A3'") (class "Default")
      (node (ref "U2") (pin "9") (pinfunction "A3_9") (pintype "input"))
      (node (ref "U3") (pin "2") (pinfunction "PE3_2") (pintype "bidirectional"))
      (node (ref "U6") (pin "P88") (pinfunction "IO_L42P_GCLK7_1_P88") (pintype "bidirectional"))
    )
    (net (code "15") (name "A3_5") (class "Default")
      (node (ref "10B") (pin "1") (pinfunction "P_1") (pintype "passive"))
      (node (ref "U8") (pin "16") (pinfunction "B4_16") (pintype "bidirectional"))
    )
    (net (code "16") (name "A4") (class "Default")
      (node (ref "U11") (pin "5") (pinfunction "A4_5") (pintype "bidirectional"))
      (node (ref "U6") (pin "P69") (pinfunction "IO_L1N_M0_CMPMISO_2_P69") (pintype "bidirectional"))
    )
    (net (code "17") (name "A4'") (class "Default")
      (node (ref "U2") (pin "8") (pinfunction "A4_8") (pintype "input"))
      (node (ref "U3") (pin "3") (pinfunction "PE4_3") (pintype "bidirectional"))
      (node (ref "U6") (pin "P93") (pinfunction "IO_L41P_GCLK9_IRDY1_1_P93") (pintype "bidirectional"))
    )
    (net (code "18") (name "A4_5") (class "Default")
      (node (ref "22B") (pin "1") (pinfunction "P_1") (pintype "passive"))
      (node (ref "U11") (pin "16") (pinfunction "B4_16") (pintype "bidirectional"))
    )
    (net (code "19") (name "A5") (class "Default")
      (node (ref "U11") (pin "7") (pinfunction "A6_7") (pintype "bidirectional"))
      (node (ref "U6") (pin "P66") (pinfunction "IO_L2N_CMPMOSI_2_P66") (pintype "bidirectional"))
    )
    (net (code "20") (name "A5'") (class "Default")
      (node (ref "U2") (pin "7") (pinfunction "A5_7") (pintype "input"))
      (node (ref "U3") (pin "4") (pinfunction "PE5_4") (pintype "bidirectional"))
      (node (ref "U6") (pin "P95") (pinfunction "IO_L40P_GCLK11_1_P95") (pintype "bidirectional"))
    )
    (net (code "21") (name "A5_5") (class "Default")
      (node (ref "21B") (pin "1") (pinfunction "P_1") (pintype "passive"))
      (node (ref "U11") (pin "14") (pinfunction "B6_14") (pintype "bidirectional"))
    )
    (net (code "22") (name "A6") (class "Default")
      (node (ref "U6") (pin "P41") (pinfunction "IO_L64P_D8_2_P41") (pintype "bidirectional"))
      (node (ref "U8") (pin "4") (pinfunction "A3_4") (pintype "bidirectional"))
    )
    (net (code "23") (name "A6'") (class "Default")
      (node (ref "U2") (pin "6") (pinfunction "A6_6") (pintype "input"))
      (node (ref "U3") (pin "5") (pinfunction "PE6_5") (pintype "bidirectional"))
      (node (ref "U6") (pin "P99") (pinfunction "IO_L33N_1_P99") (pintype "bidirectional"))
    )
    (net (code "24") (name "A6_5") (class "Default")
      (node (ref "11A") (pin "1") (pinfunction "P_1") (pintype "passive"))
      (node (ref "20B") (pin "1") (pinfunction "P_1") (pintype "passive"))
      (node (ref "U8") (pin "17") (pinfunction "B3_17") (pintype "bidirectional"))
    )
    (net (code "25") (name "A7") (class "Default")
      (node (ref "U10") (pin "3") (pinfunction "A2_3") (pintype "bidirectional"))
      (node (ref "U6") (pin "P62") (pinfunction "IO_L12P_D1_MISO2_2_P62") (pintype "bidirectional"))
    )
    (net (code "26") (name "A7'") (class "Default")
      (node (ref "U2") (pin "5") (pinfunction "A7_5") (pintype "input"))
      (node (ref "U3") (pin "38") (pinfunction "PE7_38") (pintype "bidirectional"))
      (node (ref "U6") (pin "P101") (pinfunction "IO_L32N_1_P101") (pintype "bidirectional"))
    )
    (net (code "27") (name "A7_5") (class "Default")
      (node (ref "19B") (pin "1") (pinfunction "P_1") (pintype "passive"))
      (node (ref "U10") (pin "18") (pinfunction "B2_18") (pintype "bidirectional"))
    )
    (net (code "28") (name "A8") (class "Default")
      (node (ref "U10") (pin "5") (pinfunction "A4_5") (pintype "bidirectional"))
      (node (ref "U6") (pin "P60") (pinfunction "IO_L13P_M1_2_P60") (pintype "bidirectional"))
    )
    (net (code "29") (name "A8'") (class "Default")
      (node (ref "U2") (pin "27") (pinfunction "A8_27") (pintype "input"))
      (node (ref "U3") (pin "39") (pinfunction "PE8_39") (pintype "bidirectional"))
      (node (ref "U6") (pin "P98") (pinfunction "IO_L34P_1_P98") (pintype "bidirectional"))
    )
    (net (code "30") (name "A8_5") (class "Default")
      (node (ref "18B") (pin "1") (pinfunction "P_1") (pintype "passive"))
      (node (ref "U10") (pin "16") (pinfunction "B4_16") (pintype "bidirectional"))
    )
    (net (code "31") (name "A9") (class "Default")
      (node (ref "U10") (pin "7") (pinfunction "A6_7") (pintype "bidirectional"))
      (node (ref "U6") (pin "P59") (pinfunction "IO_L13N_D10_2_P59") (pintype "bidirectional"))
    )
    (net (code "32") (name "A9'") (class "Default")
      (node (ref "U2") (pin "26") (pinfunction "A9_26") (pintype "input"))
      (node (ref "U3") (pin "40") (pinfunction "PE9_40") (pintype "bidirectional"))
      (node (ref "U6") (pin "P97") (pinfunction "IO_L34N_1_P97") (pintype "bidirectional"))
    )
    (net (code "33") (name "A9_5") (class "Default")
      (node (ref "17B") (pin "1") (pinfunction "P_1") (pintype "passive"))
      (node (ref "U10") (pin "14") (pinfunction "B6_14") (pintype "bidirectional"))
    )
    (net (code "34") (name "A10") (class "Default")
      (node (ref "U10") (pin "9") (pinfunction "A8_9") (pintype "bidirectional"))
      (node (ref "U6") (pin "P57") (pinfunction "IO_L14N_D12_2_P57") (pintype "bidirectional"))
    )
    (net (code "35") (name "A10'") (class "Default")
      (node (ref "U2") (pin "23") (pinfunction "A10_23") (pintype "input"))
      (node (ref "U3") (pin "41") (pinfunction "PE10_41") (pintype "bidirectional"))
      (node (ref "U6") (pin "P87") (pinfunction "IO_L42N_GCLK6_TRDY1_1_P87") (pintype "bidirectional"))
    )
    (net (code "36") (name "A10_5") (class "Default")
      (node (ref "16B") (pin "1") (pinfunction "P_1") (pintype "passive"))
      (node (ref "U10") (pin "12") (pinfunction "B8_12") (pintype "bidirectional"))
    )
    (net (code "37") (name "A11") (class "Default")
      (node (ref "U6") (pin "P55") (pinfunction "IO_L30N_GCLK0_USERCCLK_2_P55") (pintype "bidirectional"))
      (node (ref "U9") (pin "3") (pinfunction "A2_3") (pintype "bidirectional"))
    )
    (net (code "38") (name "A11'") (class "Default")
      (node (ref "U2") (pin "25") (pinfunction "A11_25") (pintype "input"))
      (node (ref "U3") (pin "42") (pinfunction "PE11_42") (pintype "bidirectional"))
      (node (ref "U6") (pin "P94") (pinfunction "IO_L40N_GCLK10_1_P94") (pintype "bidirectional"))
    )
    (net (code "39") (name "A11_5") (class "Default")
      (node (ref "15B") (pin "1") (pinfunction "P_1") (pintype "passive"))
      (node (ref "U9") (pin "18") (pinfunction "B2_18") (pintype "bidirectional"))
    )
    (net (code "40") (name "A12") (class "Default")
      (node (ref "U6") (pin "P50") (pinfunction "IO_L31N_GCLK30_D15_2_P50") (pintype "bidirectional"))
      (node (ref "U9") (pin "5") (pinfunction "A4_5") (pintype "bidirectional"))
    )
    (net (code "41") (name "A12'") (class "Default")
      (node (ref "U2") (pin "4") (pinfunction "A12_4") (pintype "input"))
      (node (ref "U3") (pin "43") (pinfunction "PE12_43") (pintype "bidirectional"))
      (node (ref "U6") (pin "P104") (pinfunction "IO_L1N_VREF_1_P104") (pintype "bidirectional"))
    )
    (net (code "42") (name "A12_5") (class "Default")
      (node (ref "14B") (pin "1") (pinfunction "P_1") (pintype "passive"))
      (node (ref "U9") (pin "16") (pinfunction "B4_16") (pintype "bidirectional"))
    )
    (net (code "43") (name "A13") (class "Default")
      (node (ref "U6") (pin "P47") (pinfunction "IO_L48N_RDWR_B_VREF_2_P47") (pintype "bidirectional"))
      (node (ref "U9") (pin "7") (pinfunction "A6_7") (pintype "bidirectional"))
    )
    (net (code "44") (name "A13'") (class "Default")
      (node (ref "U2") (pin "28") (pinfunction "A13_28") (pintype "input"))
      (node (ref "U3") (pin "44") (pinfunction "PE13_44") (pintype "bidirectional"))
      (node (ref "U6") (pin "P100") (pinfunction "IO_L33P_1_P100") (pintype "bidirectional"))
    )
    (net (code "45") (name "A13_5") (class "Default")
      (node (ref "13B") (pin "1") (pinfunction "P_1") (pintype "passive"))
      (node (ref "U9") (pin "14") (pinfunction "B6_14") (pintype "bidirectional"))
    )
    (net (code "46") (name "A14") (class "Default")
      (node (ref "U6") (pin "P45") (pinfunction "IO_L49N_D4_2_P45") (pintype "bidirectional"))
      (node (ref "U9") (pin "9") (pinfunction "A8_9") (pintype "bidirectional"))
    )
    (net (code "47") (name "A14'") (class "Default")
      (node (ref "U2") (pin "3") (pinfunction "A14_3") (pintype "input"))
      (node (ref "U3") (pin "45") (pinfunction "PE14_45") (pintype "bidirectional"))
      (node (ref "U6") (pin "P111") (pinfunction "IO_L66N_SCP0_0_P111") (pintype "bidirectional"))
    )
    (net (code "48") (name "A14_5") (class "Default")
      (node (ref "12B") (pin "1") (pinfunction "P_1") (pintype "passive"))
      (node (ref "U9") (pin "12") (pinfunction "B8_12") (pintype "bidirectional"))
    )
    (net (code "49") (name "A15") (class "Default")
      (node (ref "U6") (pin "P43") (pinfunction "IO_L62N_D6_2_P43") (pintype "bidirectional"))
      (node (ref "U8") (pin "3") (pinfunction "A2_3") (pintype "bidirectional"))
    )
    (net (code "50") (name "A15'") (class "Default")
      (node (ref "U2") (pin "31") (pinfunction "A15_31") (pintype "input"))
      (node (ref "U3") (pin "46") (pinfunction "PE15_46") (pintype "bidirectional"))
      (node (ref "U6") (pin "P112") (pinfunction "IO_L66P_SCP1_0_P112") (pintype "bidirectional"))
    )
    (net (code "51") (name "A15_5") (class "Default")
      (node (ref "11B") (pin "1") (pinfunction "P_1") (pintype "passive"))
      (node (ref "U8") (pin "18") (pinfunction "B2_18") (pintype "bidirectional"))
    )
    (net (code "52") (name "A16'") (class "Default")
      (node (ref "U2") (pin "2") (pinfunction "A16_2") (pintype "input"))
      (node (ref "U3") (pin "48") (pinfunction "PB11_48") (pintype "bidirectional"))
      (node (ref "U6") (pin "P114") (pinfunction "IO_L65N_SCP2_0_P114") (pintype "bidirectional"))
    )
    (net (code "53") (name "A17'") (class "Default")
      (node (ref "U2") (pin "30") (pinfunction "A17_30") (pintype "input"))
      (node (ref "U3") (pin "51") (pinfunction "PB12_51") (pintype "bidirectional"))
      (node (ref "U6") (pin "P61") (pinfunction "IO_L12N_D2_MISO3_2_P61") (pintype "bidirectional"))
    )
    (net (code "54") (name "A18'") (class "Default")
      (node (ref "U2") (pin "1") (pinfunction "A18_1") (pintype "input"))
      (node (ref "U3") (pin "52") (pinfunction "PB13_52") (pintype "bidirectional"))
      (node (ref "U6") (pin "P115") (pinfunction "IO_L65P_SCP3_0_P115") (pintype "bidirectional"))
    )
    (net (code "55") (name "B0") (class "Default")
      (node (ref "U3") (pin "55") (pinfunction "PD8_55") (pintype "bidirectional"))
      (node (ref "U6") (pin "P116") (pinfunction "IO_L64N_SCP4_0_P116") (pintype "bidirectional"))
    )
    (net (code "56") (name "B1") (class "Default")
      (node (ref "U3") (pin "56") (pinfunction "PD9_56") (pintype "bidirectional"))
      (node (ref "U6") (pin "P117") (pinfunction "IO_L64P_SCP5_0_P117") (pintype "bidirectional"))
    )
    (net (code "57") (name "B2") (class "Default")
      (node (ref "U3") (pin "57") (pinfunction "PD10_57") (pintype "bidirectional"))
      (node (ref "U6") (pin "P118") (pinfunction "IO_L63N_SCP6_0_P118") (pintype "bidirectional"))
    )
    (net (code "58") (name "B3") (class "Default")
      (node (ref "U3") (pin "58") (pinfunction "PD11_58") (pintype "bidirectional"))
      (node (ref "U6") (pin "P119") (pinfunction "IO_L63P_SCP7_0_P119") (pintype "bidirectional"))
    )
    (net (code "59") (name "B4") (class "Default")
      (node (ref "U3") (pin "59") (pinfunction "PD12_59") (pintype "bidirectional"))
      (node (ref "U6") (pin "P120") (pinfunction "IO_L62N_VREF_0_P120") (pintype "bidirectional"))
    )
    (net (code "60") (name "B5") (class "Default")
      (node (ref "U3") (pin "60") (pinfunction "PD13_60") (pintype "bidirectional"))
      (node (ref "U6") (pin "P121") (pinfunction "IO_L62P_0_P121") (pintype "bidirectional"))
    )
    (net (code "61") (name "B6") (class "Default")
      (node (ref "U3") (pin "61") (pinfunction "PD14_61") (pintype "bidirectional"))
      (node (ref "U6") (pin "P123") (pinfunction "IO_L37N_GCLK12_0_P123") (pintype "bidirectional"))
    )
    (net (code "62") (name "B7") (class "Default")
      (node (ref "U3") (pin "62") (pinfunction "PD15_62") (pintype "bidirectional"))
      (node (ref "U6") (pin "P124") (pinfunction "IO_L37P_GCLK13_0_P124") (pintype "bidirectional"))
    )
    (net (code "63") (name "BOOT0") (class "Default")
      (node (ref "R24") (pin "1") (pinfunction "1_1") (pintype "passive"))
      (node (ref "R30") (pin "2") (pinfunction "2_2") (pintype "passive"))
      (node (ref "U3") (pin "94") (pinfunction "BOOT0_94") (pintype "bidirectional"))
    )
    (net (code "64") (name "BRIGHT") (class "Default")
      (node (ref "R33") (pin "1") (pinfunction "1_1") (pintype "passive"))
      (node (ref "R34") (pin "1") (pinfunction "1_1") (pintype "passive"))
      (node (ref "R35") (pin "1") (pinfunction "1_1") (pintype "passive"))
      (node (ref "U6") (pin "P11") (pinfunction "IO_L49N_3_P11") (pintype "bidirectional"))
    )
    (net (code "65") (name "CC1") (class "Default")
      (node (ref "J3") (pin "A5") (pinfunction "CC1_A5") (pintype "bidirectional"))
    )
    (net (code "66") (name "CC2") (class "Default")
      (node (ref "J3") (pin "B5") (pinfunction "CC2_B5") (pintype "bidirectional"))
    )
    (net (code "67") (name "CFG_CLK") (class "Default")
      (node (ref "U3") (pin "35") (pinfunction "PB0_35") (pintype "bidirectional"))
      (node (ref "U6") (pin "P17") (pinfunction "IO_L43P_GCLK23_3_P17") (pintype "bidirectional"))
    )
    (net (code "68") (name "CFG_DATA") (class "Default")
      (node (ref "U3") (pin "89") (pinfunction "PB3_89") (pintype "bidirectional"))
      (node (ref "U6") (pin "P15") (pinfunction "IO_L44P_GCLK21_3_P15") (pintype "bidirectional"))
    )
    (net (code "69") (name "CFG_RESET") (class "Default")
      (node (ref "U3") (pin "36") (pinfunction "PB1_36") (pintype "bidirectional"))
      (node (ref "U6") (pin "P16") (pinfunction "IO_L43N_GCLK22_IRDY2_3_P16") (pintype "bidirectional"))
    )
    (net (code "70") (name "COMPOSITE") (class "Default")
      (node (ref "R4") (pin "1") (pinfunction "1_1") (pintype "passive"))
      (node (ref "X1") (pin "19") (pinfunction "19_19") (pintype "passive"))
      (node (ref "X2") (pin "2") (pinfunction "1_2") (pintype "passive"))
    )
    (net (code "71") (name "CSYNC") (class "Default")
      (node (ref "SJ1") (pin "1") (pinfunction "1_1") (pintype "passive"))
      (node (ref "U1") (pin "16") (pinfunction "HSYNC_16") (pintype "input"))
      (node (ref "U6") (pin "P10") (pinfunction "IO_L50P_3_P10") (pintype "bidirectional"))
    )
    (net (code "72") (name "CS_LLS") (class "Default")
      (node (ref "MICRO_SD1") (pin "2") (pinfunction "CD/DAT3_2") (pintype "bidirectional"))
      (node (ref "R21") (pin "2") (pinfunction "2_2") (pintype "passive"))
    )
    (net (code "73") (name "CTRL_CLK") (class "Default")
      (node (ref "U3") (pin "90") (pinfunction "PB4_90") (pintype "bidirectional"))
      (node (ref "U6") (pin "P6") (pinfunction "IO_L52P_3_P6") (pintype "bidirectional"))
    )
    (net (code "74") (name "D0") (class "Default")
      (node (ref "U2") (pin "13") (pinfunction "DQ0_13") (pintype "output"))
      (node (ref "U6") (pin "P23") (pinfunction "IO_L41N_GCLK26_3_P23") (pintype "bidirectional"))
      (node (ref "U7") (pin "8") (pinfunction "A7_8") (pintype "bidirectional"))
    )
    (net (code "75") (name "D0_5") (class "Default")
      (node (ref "4A") (pin "1") (pinfunction "P_1") (pintype "passive"))
      (node (ref "U7") (pin "13") (pinfunction "B7_13") (pintype "bidirectional"))
    )
    (net (code "76") (name "D1") (class "Default")
      (node (ref "U2") (pin "14") (pinfunction "DQ1_14") (pintype "output"))
      (node (ref "U6") (pin "P26") (pinfunction "IO_L37N_3_P26") (pintype "bidirectional"))
      (node (ref "U7") (pin "7") (pinfunction "A6_7") (pintype "bidirectional"))
    )
    (net (code "77") (name "D1_5") (class "Default")
      (node (ref "5A") (pin "1") (pinfunction "P_1") (pintype "passive"))
      (node (ref "U7") (pin "14") (pinfunction "B6_14") (pintype "bidirectional"))
    )
    (net (code "78") (name "D2") (class "Default")
      (node (ref "U2") (pin "15") (pinfunction "DQ2_15") (pintype "output"))
      (node (ref "U6") (pin "P27") (pinfunction "IO_L37P_3_P27") (pintype "bidirectional"))
      (node (ref "U7") (pin "6") (pinfunction "A5_6") (pintype "bidirectional"))
    )
    (net (code "79") (name "D2_5") (class "Default")
      (node (ref "6A") (pin "1") (pinfunction "P_1") (pintype "passive"))
      (node (ref "U7") (pin "15") (pinfunction "B5_15") (pintype "bidirectional"))
    )
    (net (code "80") (name "D3") (class "Default")
      (node (ref "U2") (pin "17") (pinfunction "DQ3_17") (pintype "output"))
      (node (ref "U6") (pin "P34") (pinfunction "IO_L1N_VREF_3_P34") (pintype "bidirectional"))
      (node (ref "U8") (pin "8") (pinfunction "A7_8") (pintype "bidirectional"))
    )
    (net (code "81") (name "D3_5") (class "Default")
      (node (ref "9A") (pin "1") (pinfunction "P_1") (pintype "passive"))
      (node (ref "U8") (pin "13") (pinfunction "B7_13") (pintype "bidirectional"))
    )
    (net (code "82") (name "D4") (class "Default")
      (node (ref "U2") (pin "18") (pinfunction "DQ4_18") (pintype "output"))
      (node (ref "U6") (pin "P39") (pinfunction "IO_L65P_INIT_B_2_P39") (pintype "bidirectional"))
      (node (ref "U8") (pin "6") (pinfunction "A5_6") (pintype "bidirectional"))
    )
    (net (code "83") (name "D4_5") (class "Default")
      (node (ref "10A") (pin "1") (pinfunction "P_1") (pintype "passive"))
      (node (ref "U8") (pin "15") (pinfunction "B5_15") (pintype "bidirectional"))
    )
    (net (code "84") (name "D5") (class "Default")
      (node (ref "U2") (pin "19") (pinfunction "DQ5_19") (pintype "output"))
      (node (ref "U6") (pin "P32") (pinfunction "IO_L2N_3_P32") (pintype "bidirectional"))
      (node (ref "U7") (pin "1") (pinfunction "A1_1") (pintype "bidirectional"))
    )
    (net (code "85") (name "D5_5") (class "Default")
      (node (ref "8A") (pin "1") (pinfunction "P_1") (pintype "passive"))
      (node (ref "U7") (pin "20") (pinfunction "B1_20") (pintype "bidirectional"))
    )
    (net (code "86") (name "D6") (class "Default")
      (node (ref "U2") (pin "20") (pinfunction "DQ6_20") (pintype "output"))
      (node (ref "U6") (pin "P29") (pinfunction "IO_L36N_3_P29") (pintype "bidirectional"))
      (node (ref "U7") (pin "4") (pinfunction "A3_4") (pintype "bidirectional"))
    )
    (net (code "87") (name "D6_5") (class "Default")
      (node (ref "7A") (pin "1") (pinfunction "P_1") (pintype "passive"))
      (node (ref "U7") (pin "17") (pinfunction "B3_17") (pintype "bidirectional"))
    )
    (net (code "88") (name "D7") (class "Default")
      (node (ref "U2") (pin "21") (pinfunction "DQ7_21") (pintype "output"))
      (node (ref "U6") (pin "P21") (pinfunction "IO_L42N_GCLK24_3_P21") (pintype "bidirectional"))
      (node (ref "U7") (pin "9") (pinfunction "A8_9") (pintype "bidirectional"))
    )
    (net (code "89") (name "D7_5") (class "Default")
      (node (ref "1A") (pin "1") (pinfunction "P_1") (pintype "passive"))
      (node (ref "U7") (pin "12") (pinfunction "B8_12") (pintype "bidirectional"))
    )
    (net (code "90") (name "DI_LLS") (class "Default")
      (node (ref "MICRO_SD1") (pin "3") (pinfunction "CMD_3") (pintype "bidirectional"))
      (node (ref "R17") (pin "2") (pinfunction "2_2") (pintype "passive"))
    )
    (net (code "91") (name "DOWN") (class "Default")
      (node (ref "J2") (pin "2") (pinfunction "2_2") (pintype "passive"))
      (node (ref "U6") (pin "P79") (pinfunction "IO_L47P_1_P79") (pintype "bidirectional"))
    )
    (net (code "92") (name "EN_M1_NOT") (class "Default")
      (node (ref "U3") (pin "25") (pinfunction "PA2_25") (pintype "bidirectional"))
      (node (ref "U6") (pin "P140") (pinfunction "IO_L3P_0_P140") (pintype "bidirectional"))
    )
    (net (code "93") (name "FIRE") (class "Default")
      (node (ref "J2") (pin "6") (pinfunction "6_6") (pintype "passive"))
      (node (ref "U6") (pin "P82") (pinfunction "IO_L45N_1_P82") (pintype "bidirectional"))
    )
    (net (code "94") (name "FLASH_CS") (class "Default")
      (node (ref "U4") (pin "1") (pinfunction "CS_1") (pintype "bidirectional"))
      (node (ref "U6") (pin "P38") (pinfunction "IO_L65N_CSO_B_2_P38") (pintype "bidirectional"))
    )
    (net (code "95") (name "FLASH_MISO") (class "Default")
      (node (ref "U4") (pin "2") (pinfunction "MISO_2") (pintype "bidirectional"))
      (node (ref "U6") (pin "P65") (pinfunction "IO_L3P_D0_DIN_MISO_MISO1_2_P65") (pintype "bidirectional"))
    )
    (net (code "96") (name "FLASH_MOSI") (class "Default")
      (node (ref "U4") (pin "5") (pinfunction "MOSI_5") (pintype "bidirectional"))
      (node (ref "U6") (pin "P64") (pinfunction "IO_L3N_MOSI_CSI_B_MISO0_2_P64") (pintype "bidirectional"))
    )
    (net (code "97") (name "FLASH_SCLK") (class "Default")
      (node (ref "U4") (pin "6") (pinfunction "SCK_6") (pintype "bidirectional"))
      (node (ref "U6") (pin "P70") (pinfunction "IO_L1P_CCLK_2_P70") (pintype "bidirectional"))
    )
    (net (code "98") (name "GET_CTRL_REG") (class "Default")
      (node (ref "U3") (pin "66") (pinfunction "PC9_66") (pintype "bidirectional"))
      (node (ref "U6") (pin "P5") (pinfunction "IO_L52N_3_P5") (pintype "bidirectional"))
    )
    (net (code "99") (name "GET_DATA_REG") (class "Default")
      (node (ref "U3") (pin "78") (pinfunction "PC10_78") (pintype "bidirectional"))
      (node (ref "U6") (pin "P2") (pinfunction "IO_L83P_3_P2") (pintype "bidirectional"))
    )
    (net (code "100") (name "GND") (class "Default")
      (node (ref "4B") (pin "1") (pinfunction "P_1") (pintype "passive"))
      (node (ref "5B") (pin "1") (pinfunction "P_1") (pintype "passive"))
      (node (ref "BT1") (pin "N") (pinfunction "NEG_N") (pintype "passive"))
      (node (ref "C10") (pin "2") (pinfunction "2_2") (pintype "passive"))
      (node (ref "C11") (pin "1") (pinfunction "1_1") (pintype "passive"))
      (node (ref "C12") (pin "1") (pinfunction "1_1") (pintype "passive"))
      (node (ref "C18") (pin "2") (pinfunction "2_2") (pintype "passive"))
      (node (ref "C19") (pin "2") (pinfunction "2_2") (pintype "passive"))
      (node (ref "C2") (pin "2") (pinfunction "2_2") (pintype "passive"))
      (node (ref "C22") (pin "1") (pinfunction "1_1") (pintype "passive"))
      (node (ref "C23") (pin "1") (pinfunction "1_1") (pintype "passive"))
      (node (ref "C24") (pin "2") (pinfunction "2_2") (pintype "passive"))
      (node (ref "C25") (pin "2") (pinfunction "2_2") (pintype "passive"))
      (node (ref "C26") (pin "2") (pinfunction "2_2") (pintype "passive"))
      (node (ref "C3") (pin "2") (pinfunction "2_2") (pintype "passive"))
      (node (ref "C33") (pin "2") (pinfunction "2_2") (pintype "passive"))
      (node (ref "C4") (pin "1") (pinfunction "1_1") (pintype "passive"))
      (node (ref "C5") (pin "1") (pinfunction "1_1") (pintype "passive"))
      (node (ref "C6") (pin "2") (pinfunction "2_2") (pintype "passive"))
      (node (ref "C7") (pin "2") (pinfunction "2_2") (pintype "passive"))
      (node (ref "C8") (pin "1") (pinfunction "1_1") (pintype "passive"))
      (node (ref "C9") (pin "1") (pinfunction "1_1") (pintype "passive"))
      (node (ref "IC2") (pin "1") (pinfunction "GND_1") (pintype "power_in"))
      (node (ref "IC5") (pin "1") (pinfunction "GND_1") (pintype "power_in"))
      (node (ref "J2") (pin "8") (pinfunction "8_8") (pintype "passive"))
      (node (ref "J3") (pin "A1_B12") (pinfunction "GND_A1_B12") (pintype "power_in"))
      (node (ref "J3") (pin "B1_A12") (pinfunction "GND_B1_A12") (pintype "power_in"))
      (node (ref "J3") (pin "SH1") (pinfunction "SHIELD_SH1") (pintype "passive"))
      (node (ref "J3") (pin "SH2") (pinfunction "SHIELD_SH2") (pintype "passive"))
      (node (ref "J3") (pin "SH3") (pinfunction "SHIELD_SH3") (pintype "passive"))
      (node (ref "J3") (pin "SH4") (pinfunction "SHIELD_SH4") (pintype "passive"))
      (node (ref "J4") (pin "1") (pinfunction "1_1") (pintype "passive"))
      (node (ref "JP4") (pin "2") (pinfunction "2_2") (pintype "passive"))
      (node (ref "JP5") (pin "2") (pinfunction "2_2") (pintype "passive"))
      (node (ref "JP6") (pin "2") (pinfunction "2_2") (pintype "passive"))
      (node (ref "JP8") (pin "2") (pinfunction "2_2") (pintype "passive"))
      (node (ref "LED3") (pin "P1") (pinfunction "C_P1") (pintype "passive"))
      (node (ref "LED3") (pin "P2") (pinfunction "C_P2") (pintype "passive"))
      (node (ref "LED3") (pin "P3") (pinfunction "C_P3") (pintype "passive"))
      (node (ref "MICRO_SD1") (pin "6") (pinfunction "VSS_6") (pintype "power_in"))
      (node (ref "MICRO_SD1") (pin "MP1") (pinfunction "SHIELD_MP1") (pintype "power_in"))
      (node (ref "MICRO_SD1") (pin "MP2") (pinfunction "SHIELD_MP2") (pintype "power_in"))
      (node (ref "MICRO_SD1") (pin "MP3") (pinfunction "SHIELD_MP3") (pintype "power_in"))
      (node (ref "MICRO_SD1") (pin "MP4") (pinfunction "SHIELD_MP4") (pintype "power_in"))
      (node (ref "R19") (pin "2") (pinfunction "2_2") (pintype "passive"))
      (node (ref "R25") (pin "1") (pinfunction "1_1") (pintype "passive"))
      (node (ref "R27") (pin "2") (pinfunction "2_2") (pintype "passive"))
      (node (ref "R28") (pin "2") (pinfunction "2_2") (pintype "passive"))
      (node (ref "R30") (pin "1") (pinfunction "1_1") (pintype "passive"))
      (node (ref "R37") (pin "2") (pinfunction "2_2") (pintype "passive"))
      (node (ref "S1") (pin "1") (pinfunction "P_1") (pintype "passive"))
      (node (ref "U1") (pin "12") (pinfunction "SELECT_12") (pintype "input"))
      (node (ref "U1") (pin "13") (pinfunction "DGND_13") (pintype "passive"))
      (node (ref "U1") (pin "2") (pinfunction "AGND_2") (pintype "passive"))
      (node (ref "U10") (pin "11") (pinfunction "GND_11") (pintype "power_in"))
      (node (ref "U11") (pin "11") (pinfunction "GND_11") (pintype "power_in"))
      (node (ref "U2") (pin "16") (pinfunction "VSS_16") (pintype "output"))
      (node (ref "U2") (pin "22") (pinfunction "CE_22") (pintype "input"))
      (node (ref "U3") (pin "10") (pinfunction "VSS_10") (pintype "bidirectional"))
      (node (ref "U3") (pin "20") (pinfunction "VSSA_20") (pintype "bidirectional"))
      (node (ref "U3") (pin "27") (pinfunction "VSS_27") (pintype "bidirectional"))
      (node (ref "U3") (pin "74") (pinfunction "VSS_74") (pintype "bidirectional"))
      (node (ref "U3") (pin "99") (pinfunction "VSS_99") (pintype "bidirectional"))
      (node (ref "U4") (pin "4") (pinfunction "GND_4") (pintype "power_in"))
      (node (ref "U5") (pin "7") (pinfunction "GND_7") (pintype "power_in"))
      (node (ref "U6") (pin "P108") (pinfunction "GND_P108") (pintype "bidirectional"))
      (node (ref "U6") (pin "P113") (pinfunction "GND_P113") (pintype "bidirectional"))
      (node (ref "U6") (pin "P13") (pinfunction "GND_P13") (pintype "bidirectional"))
      (node (ref "U6") (pin "P130") (pinfunction "GND_P130") (pintype "bidirectional"))
      (node (ref "U6") (pin "P136") (pinfunction "GND_P136") (pintype "bidirectional"))
      (node (ref "U6") (pin "P25") (pinfunction "GND_P25") (pintype "bidirectional"))
      (node (ref "U6") (pin "P3") (pinfunction "GND_P3") (pintype "bidirectional"))
      (node (ref "U6") (pin "P49") (pinfunction "GND_P49") (pintype "bidirectional"))
      (node (ref "U6") (pin "P54") (pinfunction "GND_P54") (pintype "bidirectional"))
      (node (ref "U6") (pin "P68") (pinfunction "GND_P68") (pintype "bidirectional"))
      (node (ref "U6") (pin "P73") (pinfunction "SUSPEND_P73") (pintype "bidirectional"))
      (node (ref "U6") (pin "P77") (pinfunction "GND_P77") (pintype "bidirectional"))
      (node (ref "U6") (pin "P91") (pinfunction "GND_P91") (pintype "bidirectional"))
      (node (ref "U6") (pin "P96") (pinfunction "GND_P96") (pintype "bidirectional"))
      (node (ref "U7") (pin "11") (pinfunction "GND_11") (pintype "power_in"))
      (node (ref "U8") (pin "11") (pinfunction "GND_11") (pintype "power_in"))
      (node (ref "U9") (pin "11") (pinfunction "GND_11") (pintype "power_in"))
      (node (ref "X1") (pin "13") (pinfunction "13_13") (pintype "passive"))
      (node (ref "X1") (pin "14") (pinfunction "14_14") (pintype "passive"))
      (node (ref "X1") (pin "17") (pinfunction "17_17") (pintype "passive"))
      (node (ref "X1") (pin "18") (pinfunction "18_18") (pintype "passive"))
      (node (ref "X1") (pin "21") (pinfunction "21_21") (pintype "passive"))
      (node (ref "X1") (pin "4") (pinfunction "4_4") (pintype "passive"))
      (node (ref "X1") (pin "5") (pinfunction "5_5") (pintype "passive"))
      (node (ref "X1") (pin "8") (pinfunction "8_8") (pintype "passive"))
      (node (ref "X1") (pin "9") (pinfunction "9_9") (pintype "passive"))
      (node (ref "X2") (pin "1") (pinfunction "2_1") (pintype "passive"))
    )
    (net (code "101") (name "LEDB") (class "Default")
      (node (ref "R3") (pin "1") (pinfunction "1_1") (pintype "passive"))
      (node (ref "U3") (pin "64") (pinfunction "PC7_64") (pintype "bidirectional"))
    )
    (net (code "102") (name "LEDG") (class "Default")
      (node (ref "R13") (pin "1") (pinfunction "1_1") (pintype "passive"))
      (node (ref "U3") (pin "63") (pinfunction "PC6_63") (pintype "bidirectional"))
    )
    (net (code "103") (name "LEDR") (class "Default")
      (node (ref "R2") (pin "1") (pinfunction "1_1") (pintype "passive"))
      (node (ref "U3") (pin "65") (pinfunction "PC8_65") (pintype "bidirectional"))
    )
    (net (code "104") (name "LEFT") (class "Default")
      (node (ref "J2") (pin "3") (pinfunction "3_3") (pintype "passive"))
      (node (ref "U6") (pin "P80") (pinfunction "IO_L46N_1_P80") (pintype "bidirectional"))
    )
    (net (code "105") (name "LE_IL") (class "Default")
      (node (ref "U3") (pin "7") (pinfunction "PC13_7") (pintype "bidirectional"))
      (node (ref "U6") (pin "P14") (pinfunction "IO_L44N_GCLK20_3_P14") (pintype "bidirectional"))
    )
    (net (code "106") (name "MISO") (class "Default")
      (node (ref "R20") (pin "1") (pinfunction "1_1") (pintype "passive"))
      (node (ref "U3") (pin "31") (pinfunction "PA6_31") (pintype "bidirectional"))
    )
    (net (code "107") (name "MOSI") (class "Default")
      (node (ref "R17") (pin "1") (pinfunction "1_1") (pintype "passive"))
      (node (ref "U3") (pin "32") (pinfunction "PA7_32") (pintype "bidirectional"))
    )
    (net (code "108") (name "Net-(1B-P)") (class "Default")
      (node (ref "1B") (pin "1") (pinfunction "P_1") (pintype "passive"))
      (node (ref "D4") (pin "A") (pinfunction "A_A") (pintype "passive"))
    )
    (net (code "109") (name "Net-(BT1-POS)") (class "Default")
      (node (ref "BT1") (pin "P") (pinfunction "POS_P") (pintype "passive"))
      (node (ref "D3") (pin "2") (pinfunction "A2_2") (pintype "passive"))
      (node (ref "U3") (pin "16") (pinfunction "PC1_16") (pintype "bidirectional"))
    )
    (net (code "110") (name "Net-(C1-Pad-)") (class "Default")
      (node (ref "C1") (pin "-") (pinfunction "-_-") (pintype "passive"))
      (node (ref "R4") (pin "2") (pinfunction "2_2") (pintype "passive"))
    )
    (net (code "111") (name "Net-(C9-Pad2)") (class "Default")
      (node (ref "C9") (pin "2") (pinfunction "2_2") (pintype "passive"))
      (node (ref "R5") (pin "2") (pinfunction "2_2") (pintype "passive"))
    )
    (net (code "112") (name "Net-(C13-Pad1)") (class "Default")
      (node (ref "C13") (pin "1") (pinfunction "1_1") (pintype "passive"))
      (node (ref "J4") (pin "4") (pinfunction "4_4") (pintype "passive"))
      (node (ref "J4") (pin "5") (pinfunction "5_5") (pintype "passive"))
    )
    (net (code "113") (name "Net-(C13-Pad2)") (class "Default")
      (node (ref "C13") (pin "2") (pinfunction "2_2") (pintype "passive"))
      (node (ref "R6") (pin "2") (pinfunction "2_2") (pintype "passive"))
    )
    (net (code "114") (name "Net-(C14-Pad-)") (class "Default")
      (node (ref "C14") (pin "-") (pinfunction "-_-") (pintype "passive"))
      (node (ref "JP1") (pin "2") (pinfunction "2_2") (pintype "passive"))
    )
    (net (code "115") (name "Net-(D3-CC)") (class "Default")
      (node (ref "D3") (pin "3") (pinfunction "CC_3") (pintype "passive"))
      (node (ref "U3") (pin "6") (pinfunction "VBAT_6") (pintype "bidirectional"))
    )
    (net (code "116") (name "Net-(J3-DN1)") (class "Default")
      (node (ref "J3") (pin "A7") (pinfunction "DN1_A7") (pintype "bidirectional"))
      (node (ref "J3") (pin "B7") (pinfunction "DN2_B7") (pintype "bidirectional"))
      (node (ref "R26") (pin "1") (pinfunction "1_1") (pintype "passive"))
    )
    (net (code "117") (name "Net-(J3-DP1)") (class "Default")
      (node (ref "J3") (pin "A6") (pinfunction "DP1_A6") (pintype "bidirectional"))
      (node (ref "J3") (pin "B6") (pinfunction "DP2_B6") (pintype "bidirectional"))
      (node (ref "R22") (pin "1") (pinfunction "1_1") (pintype "passive"))
      (node (ref "R23") (pin "1") (pinfunction "1_1") (pintype "passive"))
    )
    (net (code "118") (name "Net-(JP2-Pad1)") (class "Default")
      (node (ref "JP2") (pin "1") (pinfunction "1_1") (pintype "passive"))
      (node (ref "X1") (pin "16") (pinfunction "16_16") (pintype "passive"))
    )
    (net (code "119") (name "Net-(JP2-Pad2)") (class "Default")
      (node (ref "JP2") (pin "2") (pinfunction "2_2") (pintype "passive"))
      (node (ref "R36") (pin "1") (pinfunction "1_1") (pintype "passive"))
    )
    (net (code "120") (name "Net-(JP7-Pad1)") (class "Default")
      (node (ref "JP7") (pin "1") (pinfunction "1_1") (pintype "passive"))
      (node (ref "R24") (pin "2") (pinfunction "2_2") (pintype "passive"))
    )
    (net (code "121") (name "Net-(JP7-Pad3)") (class "Default")
      (node (ref "JP7") (pin "3") (pinfunction "3_3") (pintype "passive"))
      (node (ref "R16") (pin "1") (pinfunction "1_1") (pintype "passive"))
    )
    (net (code "122") (name "Net-(LED2-PadA)") (class "Default")
      (node (ref "LED2") (pin "A") (pinfunction "A_A") (pintype "passive"))
      (node (ref "R11") (pin "2") (pinfunction "2_2") (pintype "passive"))
    )
    (net (code "123") (name "Net-(LED3A-A)") (class "Default")
      (node (ref "LED3") (pin "P6") (pinfunction "A_P6") (pintype "passive"))
      (node (ref "R3") (pin "2") (pinfunction "2_2") (pintype "passive"))
    )
    (net (code "124") (name "Net-(LED3B-A)") (class "Default")
      (node (ref "LED3") (pin "P5") (pinfunction "A_P5") (pintype "passive"))
      (node (ref "R13") (pin "2") (pinfunction "2_2") (pintype "passive"))
    )
    (net (code "125") (name "Net-(LED3C-A)") (class "Default")
      (node (ref "LED3") (pin "P4") (pinfunction "A_P4") (pintype "passive"))
      (node (ref "R2") (pin "2") (pinfunction "2_2") (pintype "passive"))
    )
    (net (code "126") (name "Net-(MICRO_SD1-DAT0)") (class "Default")
      (node (ref "MICRO_SD1") (pin "7") (pinfunction "DAT0_7") (pintype "bidirectional"))
      (node (ref "R20") (pin "2") (pinfunction "2_2") (pintype "passive"))
    )
    (net (code "127") (name "Net-(Q3-2)") (class "Default")
      (node (ref "C12") (pin "2") (pinfunction "2_2") (pintype "passive"))
      (node (ref "Q3") (pin "3") (pinfunction "2_3") (pintype "passive"))
      (node (ref "R14") (pin "2") (pinfunction "2_2") (pintype "passive"))
      (node (ref "U3") (pin "13") (pinfunction "PH1_13") (pintype "bidirectional"))
    )
    (net (code "128") (name "Net-(R10-Pad2)") (class "Default")
      (node (ref "R10") (pin "2") (pinfunction "2_2") (pintype "passive"))
      (node (ref "R32") (pin "2") (pinfunction "2_2") (pintype "passive"))
      (node (ref "R35") (pin "2") (pinfunction "2_2") (pintype "passive"))
    )
    (net (code "129") (name "Net-(R29-Pad2)") (class "Default")
      (node (ref "R29") (pin "2") (pinfunction "2_2") (pintype "passive"))
      (node (ref "R33") (pin "2") (pinfunction "2_2") (pintype "passive"))
      (node (ref "R8") (pin "2") (pinfunction "2_2") (pintype "passive"))
    )
    (net (code "130") (name "Net-(R31-Pad2)") (class "Default")
      (node (ref "R31") (pin "2") (pinfunction "2_2") (pintype "passive"))
      (node (ref "R34") (pin "2") (pinfunction "2_2") (pintype "passive"))
      (node (ref "R9") (pin "2") (pinfunction "2_2") (pintype "passive"))
    )
    (net (code "131") (name "Net-(U1-COMP)") (class "Default")
      (node (ref "C1") (pin "+") (pinfunction "+_+") (pintype "passive"))
      (node (ref "SJ1") (pin "2") (pinfunction "2_2") (pintype "passive"))
      (node (ref "U1") (pin "10") (pinfunction "COMP_10") (pintype "output"))
    )
    (net (code "132") (name "Net-(U3-PC14)") (class "Default")
      (node (ref "C22") (pin "2") (pinfunction "2_2") (pintype "passive"))
      (node (ref "Q4") (pin "2") (pinfunction "2_2") (pintype "passive"))
      (node (ref "U3") (pin "8") (pinfunction "PC14_8") (pintype "bidirectional"))
    )
    (net (code "133") (name "Net-(U3-PC15)") (class "Default")
      (node (ref "C23") (pin "2") (pinfunction "2_2") (pintype "passive"))
      (node (ref "Q4") (pin "1") (pinfunction "1_1") (pintype "passive"))
      (node (ref "U3") (pin "9") (pinfunction "PC15_9") (pintype "bidirectional"))
    )
    (net (code "134") (name "Net-(U3-PH0)") (class "Default")
      (node (ref "C11") (pin "2") (pinfunction "2_2") (pintype "passive"))
      (node (ref "Q3") (pin "1") (pinfunction "1_1") (pintype "passive"))
      (node (ref "R14") (pin "1") (pinfunction "1_1") (pintype "passive"))
      (node (ref "U3") (pin "12") (pinfunction "PH0_12") (pintype "bidirectional"))
    )
    (net (code "135") (name "Net-(U3-VCAP_1)") (class "Default")
      (node (ref "C10") (pin "1") (pinfunction "1_1") (pintype "passive"))
      (node (ref "U3") (pin "49") (pinfunction "VCAP_1_49") (pintype "bidirectional"))
    )
    (net (code "136") (name "Net-(U3-VCAP_2)") (class "Default")
      (node (ref "C7") (pin "1") (pinfunction "1_1") (pintype "passive"))
      (node (ref "U3") (pin "73") (pinfunction "VCAP_2_73") (pintype "bidirectional"))
    )
    (net (code "137") (name "Net-(U5-IN+)") (class "Default")
      (node (ref "R6") (pin "1") (pinfunction "1_1") (pintype "passive"))
      (node (ref "U5") (pin "3") (pinfunction "IN+_3") (pintype "input"))
    )
    (net (code "138") (name "Net-(U5-IN-)") (class "Default")
      (node (ref "R5") (pin "1") (pinfunction "1_1") (pintype "passive"))
      (node (ref "U5") (pin "4") (pinfunction "IN-_4") (pintype "input"))
    )
    (net (code "139") (name "Net-(U5-VO+)") (class "Default")
      (node (ref "C14") (pin "+") (pinfunction "+_+") (pintype "passive"))
      (node (ref "U5") (pin "5") (pinfunction "VO+_5") (pintype "output"))
    )
    (net (code "140") (name "Net-(U5-VO-)") (class "Default")
      (node (ref "JP1") (pin "1") (pinfunction "1_1") (pintype "passive"))
      (node (ref "U5") (pin "8") (pinfunction "VO-_8") (pintype "output"))
    )
    (net (code "141") (name "Net-(U5-~{SD})") (class "Default")
      (node (ref "R7") (pin "1") (pinfunction "1_1") (pintype "passive"))
      (node (ref "U5") (pin "1") (pinfunction "~{SD}_1") (pintype "input"))
    )
    (net (code "142") (name "Net-(U6-PROGRAM_B_2)") (class "Default")
      (node (ref "R12") (pin "2") (pinfunction "2_2") (pintype "passive"))
      (node (ref "U6") (pin "P37") (pinfunction "PROGRAM_B_2_P37") (pintype "bidirectional"))
    )
    (net (code "143") (name "O0") (class "Default")
      (node (ref "U3") (pin "81") (pinfunction "PD0_81") (pintype "bidirectional"))
      (node (ref "U6") (pin "P126") (pinfunction "IO_L36N_GCLK14_0_P126") (pintype "bidirectional"))
    )
    (net (code "144") (name "O1") (class "Default")
      (node (ref "U3") (pin "82") (pinfunction "PD1_82") (pintype "bidirectional"))
      (node (ref "U6") (pin "P127") (pinfunction "IO_L36P_GCLK15_0_P127") (pintype "bidirectional"))
    )
    (net (code "145") (name "O2") (class "Default")
      (node (ref "U3") (pin "83") (pinfunction "PD2_83") (pintype "bidirectional"))
      (node (ref "U6") (pin "P131") (pinfunction "IO_L35N_GCLK16_0_P131") (pintype "bidirectional"))
    )
    (net (code "146") (name "O3") (class "Default")
      (node (ref "U3") (pin "84") (pinfunction "PD3_84") (pintype "bidirectional"))
      (node (ref "U6") (pin "P132") (pinfunction "IO_L35P_GCLK17_0_P132") (pintype "bidirectional"))
    )
    (net (code "147") (name "O4") (class "Default")
      (node (ref "U3") (pin "85") (pinfunction "PD4_85") (pintype "bidirectional"))
      (node (ref "U6") (pin "P133") (pinfunction "IO_L34N_GCLK18_0_P133") (pintype "bidirectional"))
    )
    (net (code "148") (name "O5") (class "Default")
      (node (ref "U3") (pin "86") (pinfunction "PD5_86") (pintype "bidirectional"))
      (node (ref "U6") (pin "P134") (pinfunction "IO_L34P_GCLK19_0_P134") (pintype "bidirectional"))
    )
    (net (code "149") (name "O6") (class "Default")
      (node (ref "U3") (pin "87") (pinfunction "PD6_87") (pintype "bidirectional"))
      (node (ref "U6") (pin "P137") (pinfunction "IO_L4N_0_P137") (pintype "bidirectional"))
    )
    (net (code "150") (name "O7") (class "Default")
      (node (ref "U3") (pin "88") (pinfunction "PD7_88") (pintype "bidirectional"))
      (node (ref "U6") (pin "P138") (pinfunction "IO_L4P_0_P138") (pintype "bidirectional"))
    )
    (net (code "151") (name "PA11{slash}USB_DN") (class "Default")
      (node (ref "R26") (pin "2") (pinfunction "2_2") (pintype "passive"))
      (node (ref "U3") (pin "70") (pinfunction "PA11_70") (pintype "bidirectional"))
    )
    (net (code "152") (name "PA12{slash}USB_DP") (class "Default")
      (node (ref "R23") (pin "2") (pinfunction "2_2") (pintype "passive"))
      (node (ref "U3") (pin "71") (pinfunction "PA12_71") (pintype "bidirectional"))
    )
    (net (code "153") (name "PA13{slash}JTMS{slash}SWDIO") (class "Default")
      (node (ref "JP8") (pin "1") (pinfunction "1_1") (pintype "passive"))
      (node (ref "U3") (pin "72") (pinfunction "PA13_72") (pintype "bidirectional"))
    )
    (net (code "154") (name "PA14{slash}JTCK{slash}SWCLK") (class "Default")
      (node (ref "JP8") (pin "3") (pinfunction "3_3") (pintype "passive"))
      (node (ref "U3") (pin "76") (pinfunction "PA14_76") (pintype "bidirectional"))
    )
    (net (code "155") (name "PAGE_A8") (class "Default")
      (node (ref "U3") (pin "24") (pinfunction "PA1_24") (pintype "bidirectional"))
      (node (ref "U6") (pin "P143") (pinfunction "IO_L1N_VREF_0_P143") (pintype "bidirectional"))
    )
    (net (code "156") (name "PAL-NTSC") (class "Default")
      (node (ref "U1") (pin "1") (pinfunction "STND_1") (pintype "input"))
      (node (ref "U6") (pin "P22") (pinfunction "IO_L42P_GCLK25_TRDY2_3_P22") (pintype "bidirectional"))
    )
    (net (code "157") (name "PB2{slash}BOOT1") (class "Default")
      (node (ref "R16") (pin "2") (pinfunction "2_2") (pintype "passive"))
      (node (ref "R25") (pin "2") (pinfunction "2_2") (pintype "passive"))
      (node (ref "U3") (pin "37") (pinfunction "PB2_37") (pintype "bidirectional"))
    )
    (net (code "158") (name "PS2_CLOCK") (class "Default")
      (node (ref "JP6") (pin "3") (pinfunction "3_3") (pintype "passive"))
      (node (ref "U3") (pin "80") (pinfunction "PC12_80") (pintype "bidirectional"))
    )
    (net (code "159") (name "PS2_DATA") (class "Default")
      (node (ref "JP6") (pin "4") (pinfunction "4_4") (pintype "passive"))
      (node (ref "U3") (pin "79") (pinfunction "PC11_79") (pintype "bidirectional"))
    )
    (net (code "160") (name "RESET") (class "Default")
      (node (ref "C5") (pin "2") (pinfunction "2_2") (pintype "passive"))
      (node (ref "D1") (pin "A") (pinfunction "A_A") (pintype "passive"))
      (node (ref "R15") (pin "1") (pinfunction "1_1") (pintype "passive"))
      (node (ref "S1") (pin "2") (pinfunction "S_2") (pintype "passive"))
      (node (ref "U3") (pin "14") (pinfunction "NRST_14") (pintype "bidirectional"))
    )
    (net (code "161") (name "RIGHT") (class "Default")
      (node (ref "J2") (pin "4") (pinfunction "4_4") (pintype "passive"))
      (node (ref "U6") (pin "P81") (pinfunction "IO_L46P_1_P81") (pintype "bidirectional"))
    )
    (net (code "162") (name "ROM_WR_EN") (class "Default")
      (node (ref "U3") (pin "67") (pinfunction "PA8_67") (pintype "bidirectional"))
      (node (ref "U6") (pin "P142") (pinfunction "IO_L2P_0_P142") (pintype "bidirectional"))
    )
    (net (code "163") (name "RST_CTRL_REG") (class "Default")
      (node (ref "U3") (pin "53") (pinfunction "PB14_53") (pintype "bidirectional"))
      (node (ref "U6") (pin "P1") (pinfunction "IO_L83N_VREF_3_P1") (pintype "bidirectional"))
    )
    (net (code "164") (name "RST_DATA_REG") (class "Default")
      (node (ref "U3") (pin "91") (pinfunction "PB5_91") (pintype "bidirectional"))
      (node (ref "U6") (pin "P144") (pinfunction "IO_L1P_HSWAPEN_0_P144") (pintype "bidirectional"))
    )
    (net (code "165") (name "SCK_LLS") (class "Default")
      (node (ref "MICRO_SD1") (pin "5") (pinfunction "CLK_5") (pintype "bidirectional"))
      (node (ref "R18") (pin "2") (pinfunction "2_2") (pintype "passive"))
    )
    (net (code "166") (name "SCL") (class "Default")
      (node (ref "U3") (pin "92") (pinfunction "PB6_92") (pintype "bidirectional"))
    )
    (net (code "167") (name "SCLK") (class "Default")
      (node (ref "R18") (pin "1") (pinfunction "1_1") (pintype "passive"))
      (node (ref "U3") (pin "30") (pinfunction "PA5_30") (pintype "bidirectional"))
    )
    (net (code "168") (name "SDA") (class "Default")
      (node (ref "U3") (pin "93") (pinfunction "PB7_93") (pintype "bidirectional"))
    )
    (net (code "169") (name "SD_LED") (class "Default")
      (node (ref "LED2") (pin "C") (pinfunction "C_C") (pintype "passive"))
      (node (ref "U3") (pin "15") (pinfunction "PC0_15") (pintype "bidirectional"))
    )
    (net (code "170") (name "SEL_128CHARS") (class "Default")
      (node (ref "U3") (pin "77") (pinfunction "PA15_77") (pintype "bidirectional"))
      (node (ref "U6") (pin "P141") (pinfunction "IO_L2N_0_P141") (pintype "bidirectional"))
    )
    (net (code "171") (name "SOUND") (class "Default")
      (node (ref "R1") (pin "2") (pinfunction "2_2") (pintype "passive"))
      (node (ref "U3") (pin "29") (pinfunction "PA4_29") (pintype "bidirectional"))
    )
    (net (code "172") (name "SOUND'") (class "Default")
      (node (ref "J4") (pin "2") (pinfunction "2_2") (pintype "passive"))
      (node (ref "J4") (pin "3") (pinfunction "3_3") (pintype "passive"))
      (node (ref "R1") (pin "1") (pinfunction "1_1") (pintype "passive"))
      (node (ref "R37") (pin "1") (pinfunction "1_1") (pintype "passive"))
      (node (ref "X1") (pin "1") (pinfunction "1_1") (pintype "passive"))
      (node (ref "X1") (pin "3") (pinfunction "3_3") (pintype "passive"))
    )
    (net (code "173") (name "SPARE") (class "Default")
      (node (ref "U6") (pin "P75") (pinfunction "IO_L74P_AWAKE_1_P75") (pintype "bidirectional"))
    )
    (net (code "174") (name "SS_SD") (class "Default")
      (node (ref "R21") (pin "1") (pinfunction "1_1") (pintype "passive"))
      (node (ref "U3") (pin "54") (pinfunction "PB15_54") (pintype "bidirectional"))
    )
    (net (code "175") (name "TCK") (class "Default")
      (node (ref "JP3") (pin "1") (pinfunction "1_1") (pintype "passive"))
      (node (ref "U6") (pin "P109") (pinfunction "TCK_P109") (pintype "bidirectional"))
    )
    (net (code "176") (name "TDI") (class "Default")
      (node (ref "JP3") (pin "3") (pinfunction "3_3") (pintype "passive"))
      (node (ref "U6") (pin "P110") (pinfunction "TDI_P110") (pintype "bidirectional"))
    )
    (net (code "177") (name "TDO") (class "Default")
      (node (ref "JP3") (pin "2") (pinfunction "2_2") (pintype "passive"))
      (node (ref "U6") (pin "P106") (pinfunction "TDO_P106") (pintype "bidirectional"))
    )
    (net (code "178") (name "TMS") (class "Default")
      (node (ref "JP3") (pin "4") (pinfunction "4_4") (pintype "passive"))
      (node (ref "U6") (pin "P107") (pinfunction "TMS_P107") (pintype "bidirectional"))
    )
    (net (code "179") (name "UART_RX") (class "Default")
      (node (ref "JP4") (pin "3") (pinfunction "3_3") (pintype "passive"))
      (node (ref "U3") (pin "69") (pinfunction "PA10_69") (pintype "bidirectional"))
    )
    (net (code "180") (name "UART_TX") (class "Default")
      (node (ref "JP4") (pin "4") (pinfunction "4_4") (pintype "passive"))
      (node (ref "U3") (pin "68") (pinfunction "PA9_68") (pintype "bidirectional"))
    )
    (net (code "181") (name "UP") (class "Default")
      (node (ref "J2") (pin "1") (pinfunction "1_1") (pintype "passive"))
      (node (ref "U6") (pin "P78") (pinfunction "IO_L47N_1_P78") (pintype "bidirectional"))
    )
    (net (code "182") (name "VCC") (class "Default")
      (node (ref "23B") (pin "1") (pinfunction "P_1") (pintype "passive"))
      (node (ref "2A") (pin "1") (pinfunction "P_1") (pintype "passive"))
      (node (ref "C3") (pin "1") (pinfunction "1_1") (pintype "passive"))
      (node (ref "C8") (pin "2") (pinfunction "2_2") (pintype "passive"))
      (node (ref "D1") (pin "C") (pinfunction "C_C") (pintype "passive"))
      (node (ref "D2") (pin "C") (pinfunction "C_C") (pintype "passive"))
      (node (ref "D4") (pin "C") (pinfunction "C_C") (pintype "passive"))
      (node (ref "IC2") (pin "3") (pinfunction "VIN_3") (pintype "input"))
      (node (ref "IC5") (pin "3") (pinfunction "VIN_3") (pintype "input"))
      (node (ref "JP4") (pin "1") (pinfunction "1_1") (pintype "passive"))
      (node (ref "JP6") (pin "1") (pinfunction "1_1") (pintype "passive"))
      (node (ref "R11") (pin "1") (pinfunction "1_1") (pintype "passive"))
      (node (ref "R15") (pin "2") (pinfunction "2_2") (pintype "passive"))
      (node (ref "R22") (pin "2") (pinfunction "2_2") (pintype "passive"))
      (node (ref "R7") (pin "2") (pinfunction "2_2") (pintype "passive"))
      (node (ref "U1") (pin "14") (pinfunction "DPOS_14") (pintype "power_in"))
      (node (ref "U1") (pin "15") (pinfunction "VSYNC_15") (pintype "input"))
      (node (ref "U1") (pin "4") (pinfunction "APOS_4") (pintype "power_in"))
      (node (ref "U1") (pin "5") (pinfunction "ENCD_5") (pintype "input"))
      (node (ref "U10") (pin "10") (pinfunction "OE_10") (pintype "input"))
      (node (ref "U10") (pin "19") (pinfunction "VCCB_19") (pintype "power_in"))
      (node (ref "U11") (pin "10") (pinfunction "OE_10") (pintype "input"))
      (node (ref "U11") (pin "19") (pinfunction "VCCB_19") (pintype "power_in"))
      (node (ref "U5") (pin "6") (pinfunction "VDD_6") (pintype "power_in"))
      (node (ref "U7") (pin "10") (pinfunction "OE_10") (pintype "input"))
      (node (ref "U7") (pin "19") (pinfunction "VCCB_19") (pintype "power_in"))
      (node (ref "U8") (pin "10") (pinfunction "OE_10") (pintype "input"))
      (node (ref "U8") (pin "19") (pinfunction "VCCB_19") (pintype "power_in"))
      (node (ref "U9") (pin "10") (pinfunction "OE_10") (pintype "input"))
      (node (ref "U9") (pin "19") (pinfunction "VCCB_19") (pintype "power_in"))
    )
    (net (code "183") (name "VCC_USB") (class "Default")
      (node (ref "D2") (pin "A") (pinfunction "A_A") (pintype "passive"))
      (node (ref "J3") (pin "A4_B9") (pinfunction "VBUS_A4_B9") (pintype "power_in"))
      (node (ref "J3") (pin "B4_A9") (pinfunction "VBUS_B4_A9") (pintype "power_in"))
    )
    (net (code "184") (name "VID_CLK") (class "Default")
      (node (ref "U1") (pin "3") (pinfunction "FIN_3") (pintype "input"))
      (node (ref "U6") (pin "P56") (pinfunction "IO_L30P_GCLK1_D13_2_P56") (pintype "bidirectional"))
    )
    (net (code "185") (name "V_BLUE") (class "Default")
      (node (ref "R29") (pin "1") (pinfunction "1_1") (pintype "passive"))
      (node (ref "U6") (pin "P9") (pinfunction "IO_L50N_3_P9") (pintype "bidirectional"))
    )
    (net (code "186") (name "V_BLUE'") (class "Default")
      (node (ref "R28") (pin "1") (pinfunction "1_1") (pintype "passive"))
      (node (ref "R8") (pin "1") (pinfunction "1_1") (pintype "passive"))
      (node (ref "U1") (pin "8") (pinfunction "BIN_8") (pintype "input"))
      (node (ref "X1") (pin "7") (pinfunction "7_7") (pintype "passive"))
    )
    (net (code "187") (name "V_GREEN") (class "Default")
      (node (ref "R31") (pin "1") (pinfunction "1_1") (pintype "passive"))
      (node (ref "U6") (pin "P8") (pinfunction "IO_L51P_3_P8") (pintype "bidirectional"))
    )
    (net (code "188") (name "V_GREEN'") (class "Default")
      (node (ref "R27") (pin "1") (pinfunction "1_1") (pintype "passive"))
      (node (ref "R9") (pin "1") (pinfunction "1_1") (pintype "passive"))
      (node (ref "U1") (pin "7") (pinfunction "GIN_7") (pintype "input"))
      (node (ref "X1") (pin "11") (pinfunction "11_11") (pintype "passive"))
    )
    (net (code "189") (name "V_RED") (class "Default")
      (node (ref "R32") (pin "1") (pinfunction "1_1") (pintype "passive"))
      (node (ref "U6") (pin "P7") (pinfunction "IO_L51N_3_P7") (pintype "bidirectional"))
    )
    (net (code "190") (name "V_RED'") (class "Default")
      (node (ref "R10") (pin "1") (pinfunction "1_1") (pintype "passive"))
      (node (ref "R19") (pin "1") (pinfunction "1_1") (pintype "passive"))
      (node (ref "U1") (pin "6") (pinfunction "RIN_6") (pintype "input"))
      (node (ref "X1") (pin "15") (pinfunction "15_15") (pintype "passive"))
    )
    (net (code "191") (name "unconnected-(J2-Pad5)") (class "Default")
      (node (ref "J2") (pin "5") (pinfunction "5_5") (pintype "passive"))
    )
    (net (code "192") (name "unconnected-(J2-Pad7)") (class "Default")
      (node (ref "J2") (pin "7") (pinfunction "7_7") (pintype "passive"))
    )
    (net (code "193") (name "unconnected-(J2-Pad9)") (class "Default")
      (node (ref "J2") (pin "9") (pinfunction "9_9") (pintype "passive"))
    )
    (net (code "194") (name "unconnected-(MICRO_SD1-CD-PadCD1)") (class "Default")
      (node (ref "MICRO_SD1") (pin "CD1") (pinfunction "CD_CD1") (pintype "passive"))
    )
    (net (code "195") (name "unconnected-(MICRO_SD1-DAT1-Pad8)") (class "Default")
      (node (ref "MICRO_SD1") (pin "8") (pinfunction "DAT1_8") (pintype "bidirectional"))
    )
    (net (code "196") (name "unconnected-(MICRO_SD1-DAT2-Pad1)") (class "Default")
      (node (ref "MICRO_SD1") (pin "1") (pinfunction "DAT2_1") (pintype "bidirectional"))
    )
    (net (code "197") (name "unconnected-(U1-CRMA-Pad9)") (class "Default")
      (node (ref "U1") (pin "9") (pinfunction "CRMA_9") (pintype "output"))
    )
    (net (code "198") (name "unconnected-(U1-LUMA-Pad11)") (class "Default")
      (node (ref "U1") (pin "11") (pinfunction "LUMA_11") (pintype "output"))
    )
    (net (code "199") (name "unconnected-(U3-PB8-Pad95)") (class "Default")
      (node (ref "U3") (pin "95") (pinfunction "PB8_95") (pintype "bidirectional"))
    )
    (net (code "200") (name "unconnected-(U3-PC2-Pad17)") (class "Default")
      (node (ref "U3") (pin "17") (pinfunction "PC2_17") (pintype "bidirectional"))
    )
    (net (code "201") (name "unconnected-(U3-PC3-Pad18)") (class "Default")
      (node (ref "U3") (pin "18") (pinfunction "PC3_18") (pintype "bidirectional"))
    )
    (net (code "202") (name "unconnected-(U3-PC4-Pad33)") (class "Default")
      (node (ref "U3") (pin "33") (pinfunction "PC4_33") (pintype "bidirectional"))
    )
    (net (code "203") (name "unconnected-(U3-PC5-Pad34)") (class "Default")
      (node (ref "U3") (pin "34") (pinfunction "PC5_34") (pintype "bidirectional"))
    )
    (net (code "204") (name "unconnected-(U5-NC-Pad2)") (class "Default")
      (node (ref "U5") (pin "2") (pinfunction "NC_2") (pintype "no_connect"))
    )
    (net (code "205") (name "unconnected-(U6-CMPCS_B_2-PadP72)") (class "Default")
      (node (ref "U6") (pin "P72") (pinfunction "CMPCS_B_2_P72") (pintype "bidirectional"))
    )
    (net (code "206") (name "unconnected-(U6-DONE_2-PadP71)") (class "Default")
      (node (ref "U6") (pin "P71") (pinfunction "DONE_2_P71") (pintype "bidirectional"))
    )
    (net (code "207") (name "unconnected-(U11-A1-Pad1)") (class "Default")
      (node (ref "U11") (pin "1") (pinfunction "A1_1") (pintype "bidirectional"))
    )
    (net (code "208") (name "unconnected-(U11-A2-Pad3)") (class "Default")
      (node (ref "U11") (pin "3") (pinfunction "A2_3") (pintype "bidirectional"))
    )
    (net (code "209") (name "unconnected-(U11-A8-Pad9)") (class "Default")
      (node (ref "U11") (pin "9") (pinfunction "A8_9") (pintype "bidirectional"))
    )
    (net (code "210") (name "unconnected-(U11-B1-Pad20)") (class "Default")
      (node (ref "U11") (pin "20") (pinfunction "B1_20") (pintype "bidirectional"))
    )
    (net (code "211") (name "unconnected-(U11-B2-Pad18)") (class "Default")
      (node (ref "U11") (pin "18") (pinfunction "B2_18") (pintype "bidirectional"))
    )
    (net (code "212") (name "unconnected-(U11-B8-Pad12)") (class "Default")
      (node (ref "U11") (pin "12") (pinfunction "B8_12") (pintype "bidirectional"))
    )
    (net (code "213") (name "unconnected-(X1-Pad2)") (class "Default")
      (node (ref "X1") (pin "2") (pinfunction "2_2") (pintype "passive"))
    )
    (net (code "214") (name "unconnected-(X1-Pad6)") (class "Default")
      (node (ref "X1") (pin "6") (pinfunction "6_6") (pintype "passive"))
    )
    (net (code "215") (name "unconnected-(X1-Pad10)") (class "Default")
      (node (ref "X1") (pin "10") (pinfunction "10_10") (pintype "passive"))
    )
    (net (code "216") (name "unconnected-(X1-Pad12)") (class "Default")
      (node (ref "X1") (pin "12") (pinfunction "12_12") (pintype "passive"))
    )
    (net (code "217") (name "unconnected-(X1-Pad20)") (class "Default")
      (node (ref "X1") (pin "20") (pinfunction "20_20") (pintype "passive"))
    )
    (net (code "218") (name "{slash}BUSAK") (class "Default")
      (node (ref "U10") (pin "6") (pinfunction "A5_6") (pintype "bidirectional"))
    )
    (net (code "219") (name "{slash}BUSAK_5") (class "Default")
      (node (ref "18A") (pin "1") (pinfunction "P_1") (pintype "passive"))
      (node (ref "U10") (pin "15") (pinfunction "B5_15") (pintype "bidirectional"))
    )
    (net (code "220") (name "{slash}BUSRQ") (class "Default")
      (node (ref "U10") (pin "1") (pinfunction "A1_1") (pintype "bidirectional"))
    )
    (net (code "221") (name "{slash}BUSRQ_5") (class "Default")
      (node (ref "20A") (pin "1") (pinfunction "P_1") (pintype "passive"))
      (node (ref "U10") (pin "20") (pinfunction "B1_20") (pintype "bidirectional"))
    )
    (net (code "222") (name "{slash}CLOCK") (class "Default")
      (node (ref "U6") (pin "P24") (pinfunction "IO_L41P_GCLK27_3_P24") (pintype "bidirectional"))
      (node (ref "U7") (pin "5") (pinfunction "A4_5") (pintype "bidirectional"))
    )
    (net (code "223") (name "{slash}CLOCK_5") (class "Default")
      (node (ref "6B") (pin "1") (pinfunction "P_1") (pintype "passive"))
      (node (ref "U7") (pin "16") (pinfunction "B4_16") (pintype "bidirectional"))
    )
    (net (code "224") (name "{slash}HALT") (class "Default")
      (node (ref "U6") (pin "P46") (pinfunction "IO_L49P_D3_2_P46") (pintype "bidirectional"))
      (node (ref "U9") (pin "8") (pinfunction "A7_8") (pintype "bidirectional"))
    )
    (net (code "225") (name "{slash}HALT_5") (class "Default")
      (node (ref "13A") (pin "1") (pinfunction "P_1") (pintype "passive"))
      (node (ref "U9") (pin "13") (pinfunction "B7_13") (pintype "bidirectional"))
    )
    (net (code "226") (name "{slash}IORQ") (class "Default")
      (node (ref "U6") (pin "P51") (pinfunction "IO_L31P_GCLK31_D14_2_P51") (pintype "bidirectional"))
      (node (ref "U9") (pin "4") (pinfunction "A3_4") (pintype "bidirectional"))
    )
    (net (code "227") (name "{slash}IORQ_5") (class "Default")
      (node (ref "15A") (pin "1") (pinfunction "P_1") (pintype "passive"))
      (node (ref "U9") (pin "17") (pinfunction "B3_17") (pintype "bidirectional"))
    )
    (net (code "228") (name "{slash}M1") (class "Default")
      (node (ref "U11") (pin "6") (pinfunction "A5_6") (pintype "bidirectional"))
      (node (ref "U6") (pin "P67") (pinfunction "IO_L2P_CMPCLK_2_P67") (pintype "bidirectional"))
    )
    (net (code "229") (name "{slash}M1_5") (class "Default")
      (node (ref "22A") (pin "1") (pinfunction "P_1") (pintype "passive"))
      (node (ref "U11") (pin "15") (pinfunction "B5_15") (pintype "bidirectional"))
    )
    (net (code "230") (name "{slash}MEM_OE") (class "Default")
      (node (ref "U2") (pin "24") (pinfunction "OE_24") (pintype "input"))
      (node (ref "U6") (pin "P92") (pinfunction "IO_L41N_GCLK8_1_P92") (pintype "bidirectional"))
    )
    (net (code "231") (name "{slash}MREQ") (class "Default")
      (node (ref "U6") (pin "P48") (pinfunction "IO_L48P_D7_2_P48") (pintype "bidirectional"))
      (node (ref "U9") (pin "6") (pinfunction "A5_6") (pintype "bidirectional"))
    )
    (net (code "232") (name "{slash}MREQ_5") (class "Default")
      (node (ref "14A") (pin "1") (pinfunction "P_1") (pintype "passive"))
      (node (ref "U9") (pin "15") (pinfunction "B5_15") (pintype "bidirectional"))
    )
    (net (code "233") (name "{slash}NMI") (class "Default")
      (node (ref "U6") (pin "P44") (pinfunction "IO_L62P_D5_2_P44") (pintype "bidirectional"))
      (node (ref "U8") (pin "1") (pinfunction "A1_1") (pintype "bidirectional"))
    )
    (net (code "234") (name "{slash}NMI_5") (class "Default")
      (node (ref "12A") (pin "1") (pinfunction "P_1") (pintype "passive"))
      (node (ref "U8") (pin "20") (pinfunction "B1_20") (pintype "bidirectional"))
    )
    (net (code "235") (name "{slash}OE_OL") (class "Default")
      (node (ref "U3") (pin "47") (pinfunction "PB10_47") (pintype "bidirectional"))
      (node (ref "U6") (pin "P12") (pinfunction "IO_L49P_3_P12") (pintype "bidirectional"))
    )
    (net (code "236") (name "{slash}RD") (class "Default")
      (node (ref "U6") (pin "P105") (pinfunction "IO_L1P_1_P105") (pintype "bidirectional"))
      (node (ref "U9") (pin "1") (pinfunction "A1_1") (pintype "bidirectional"))
    )
    (net (code "237") (name "{slash}RD_5") (class "Default")
      (node (ref "16A") (pin "1") (pinfunction "P_1") (pintype "passive"))
      (node (ref "U9") (pin "20") (pinfunction "B1_20") (pintype "bidirectional"))
    )
    (net (code "238") (name "{slash}RESET") (class "Default")
      (node (ref "U11") (pin "8") (pinfunction "A7_8") (pintype "bidirectional"))
      (node (ref "U3") (pin "96") (pinfunction "PB9_96") (pintype "bidirectional"))
      (node (ref "U6") (pin "P139") (pinfunction "IO_L3N_0_P139") (pintype "bidirectional"))
    )
    (net (code "239") (name "{slash}RESET_5") (class "Default")
      (node (ref "21A") (pin "1") (pinfunction "P_1") (pintype "passive"))
      (node (ref "U11") (pin "13") (pinfunction "B7_13") (pintype "bidirectional"))
    )
    (net (code "240") (name "{slash}RFSH") (class "Default")
      (node (ref "U11") (pin "4") (pinfunction "A3_4") (pintype "bidirectional"))
      (node (ref "U6") (pin "P74") (pinfunction "IO_L74N_DOUT_BUSY_1_P74") (pintype "bidirectional"))
    )
    (net (code "241") (name "{slash}RFSH_5") (class "Default")
      (node (ref "23A") (pin "1") (pinfunction "P_1") (pintype "passive"))
      (node (ref "U11") (pin "17") (pinfunction "B3_17") (pintype "bidirectional"))
    )
    (net (code "242") (name "{slash}WAIT") (class "Default")
      (node (ref "U10") (pin "4") (pinfunction "A3_4") (pintype "bidirectional"))
      (node (ref "U3") (pin "23") (pinfunction "PA0_23") (pintype "bidirectional"))
    )
    (net (code "243") (name "{slash}WAIT_5") (class "Default")
      (node (ref "19A") (pin "1") (pinfunction "P_1") (pintype "passive"))
      (node (ref "U10") (pin "17") (pinfunction "B3_17") (pintype "bidirectional"))
    )
    (net (code "244") (name "{slash}WR") (class "Default")
      (node (ref "U10") (pin "8") (pinfunction "A7_8") (pintype "bidirectional"))
      (node (ref "U6") (pin "P58") (pinfunction "IO_L14P_D11_2_P58") (pintype "bidirectional"))
    )
    (net (code "245") (name "{slash}WR'") (class "Default")
      (node (ref "U2") (pin "29") (pinfunction "WE_29") (pintype "input"))
      (node (ref "U3") (pin "26") (pinfunction "PA3_26") (pintype "bidirectional"))
      (node (ref "U6") (pin "P102") (pinfunction "IO_L32P_1_P102") (pintype "bidirectional"))
    )
    (net (code "246") (name "{slash}WR_5") (class "Default")
      (node (ref "17A") (pin "1") (pinfunction "P_1") (pintype "passive"))
      (node (ref "U10") (pin "13") (pinfunction "B7_13") (pintype "bidirectional"))
    )
  )
)
